# ARKnew.net
KiCad netlist of a schematic drawn in EAGLE
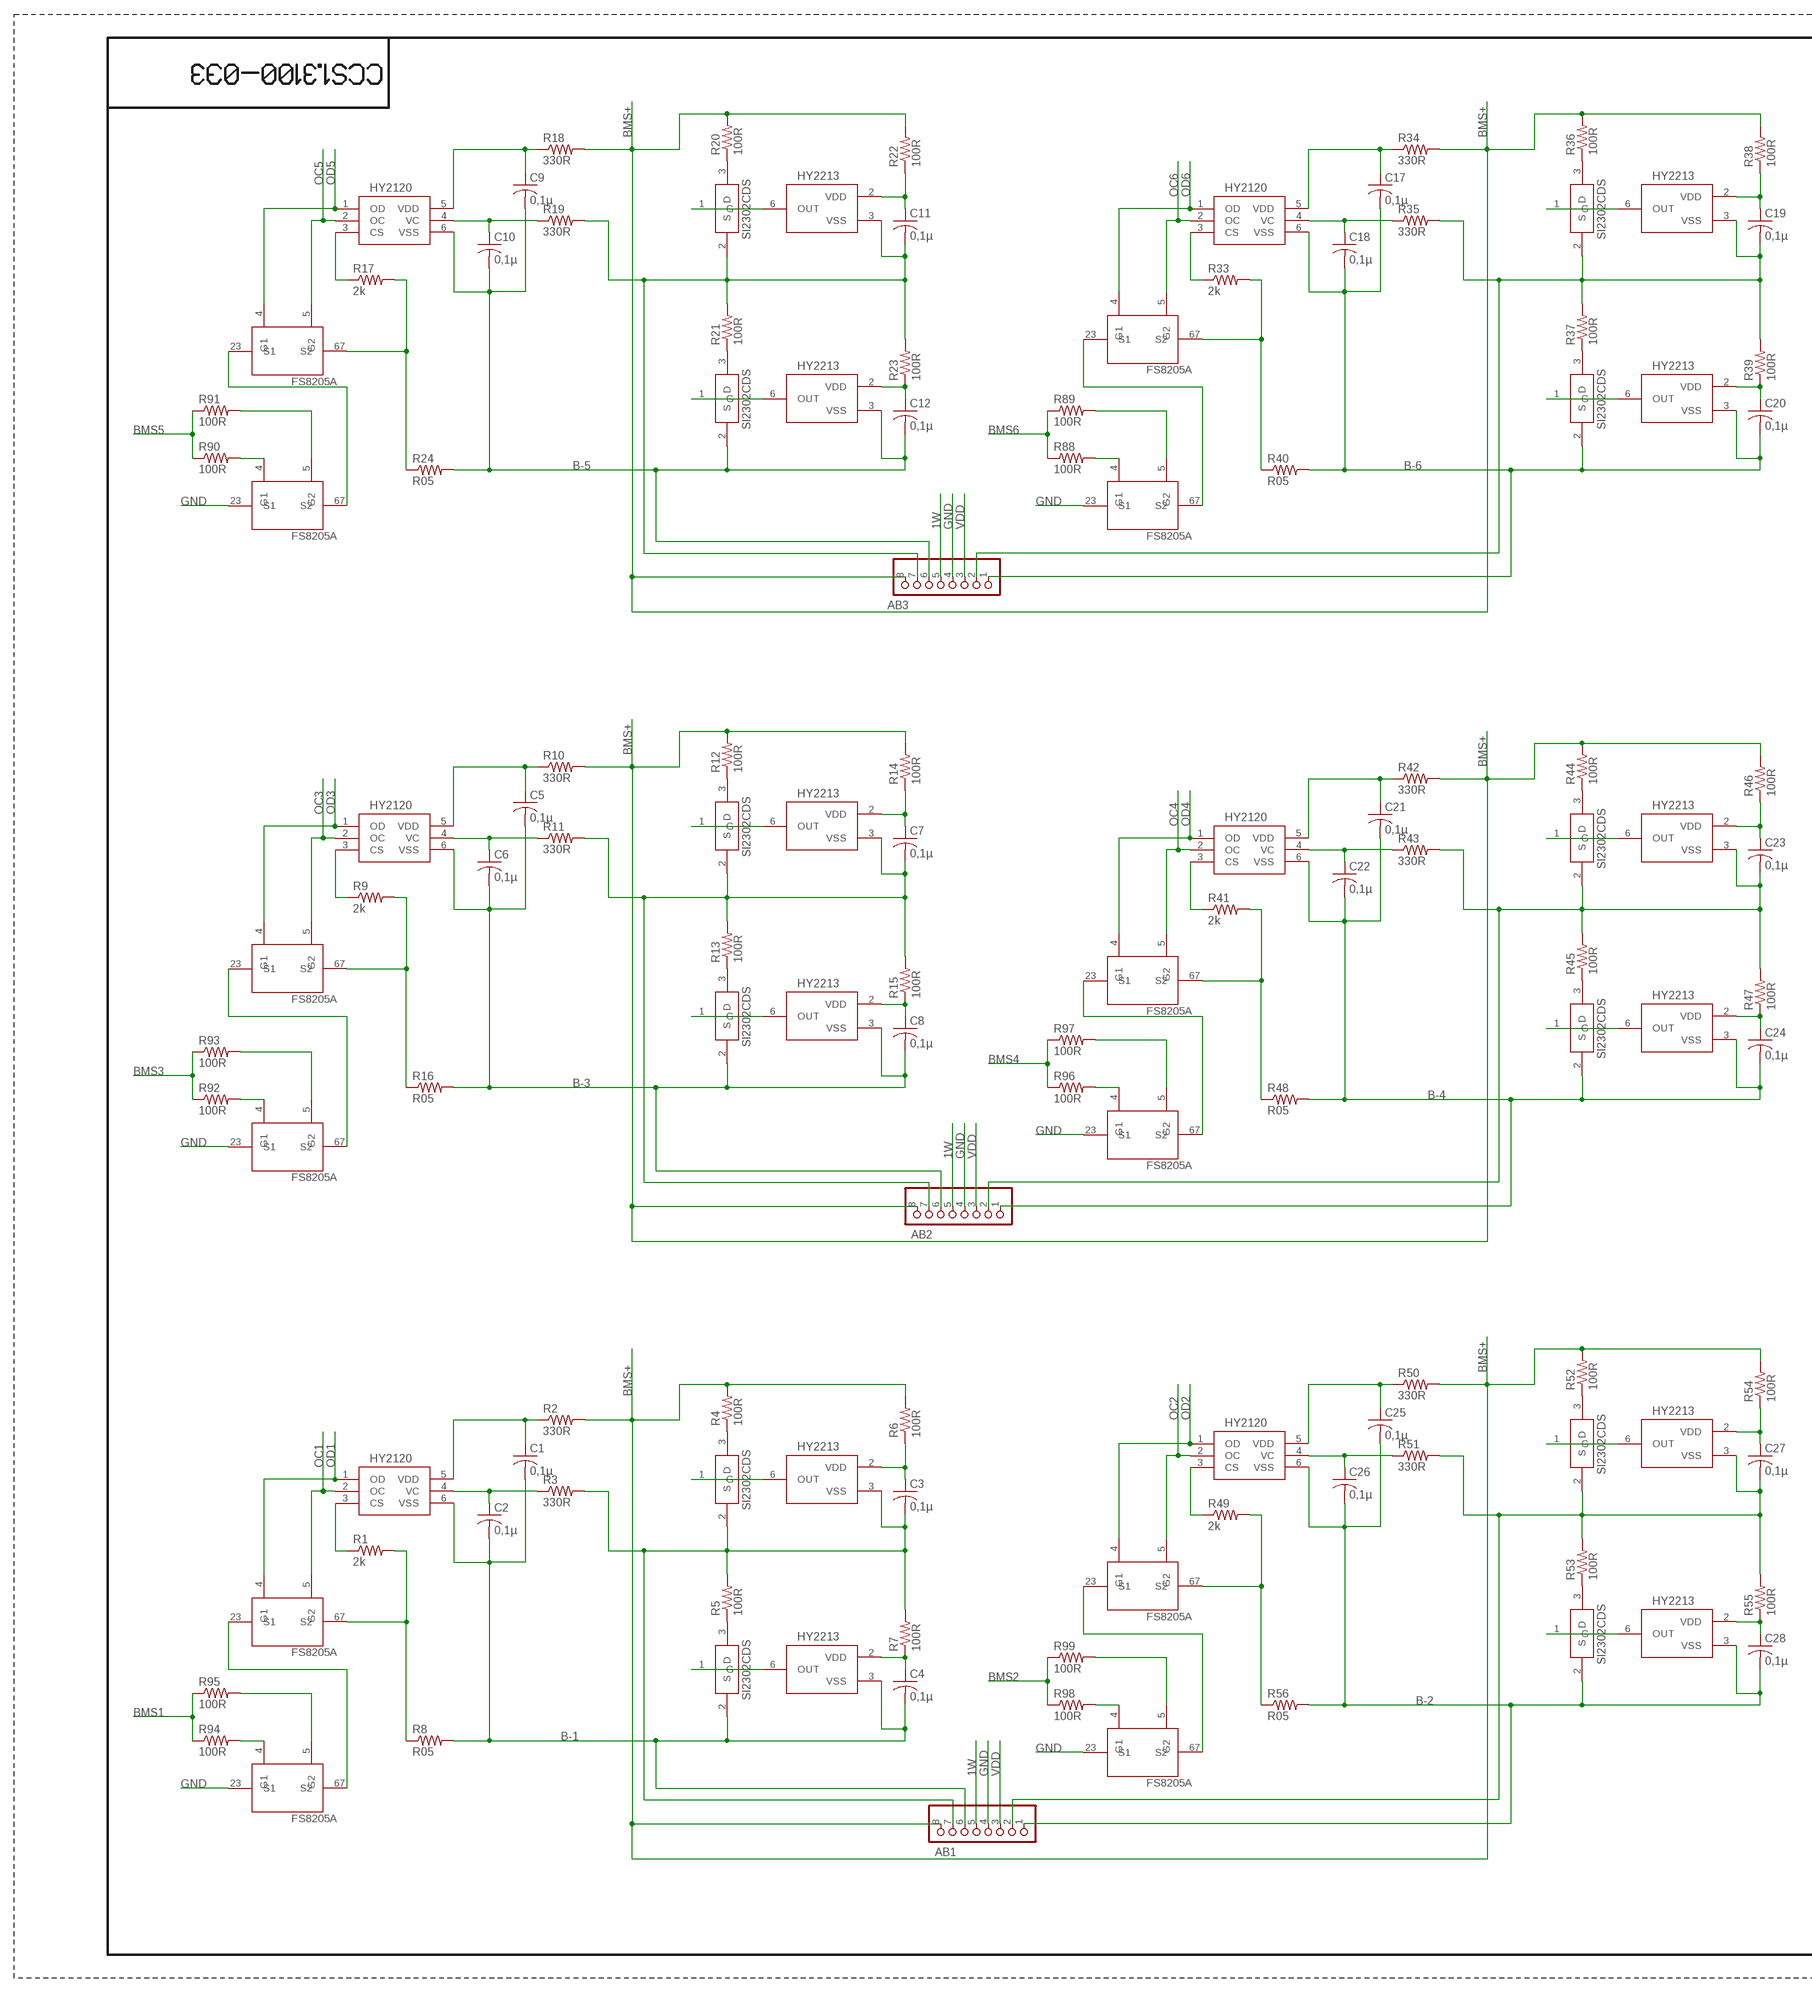
[diagram p0: schematic, sheet 1, part 1 of 2]
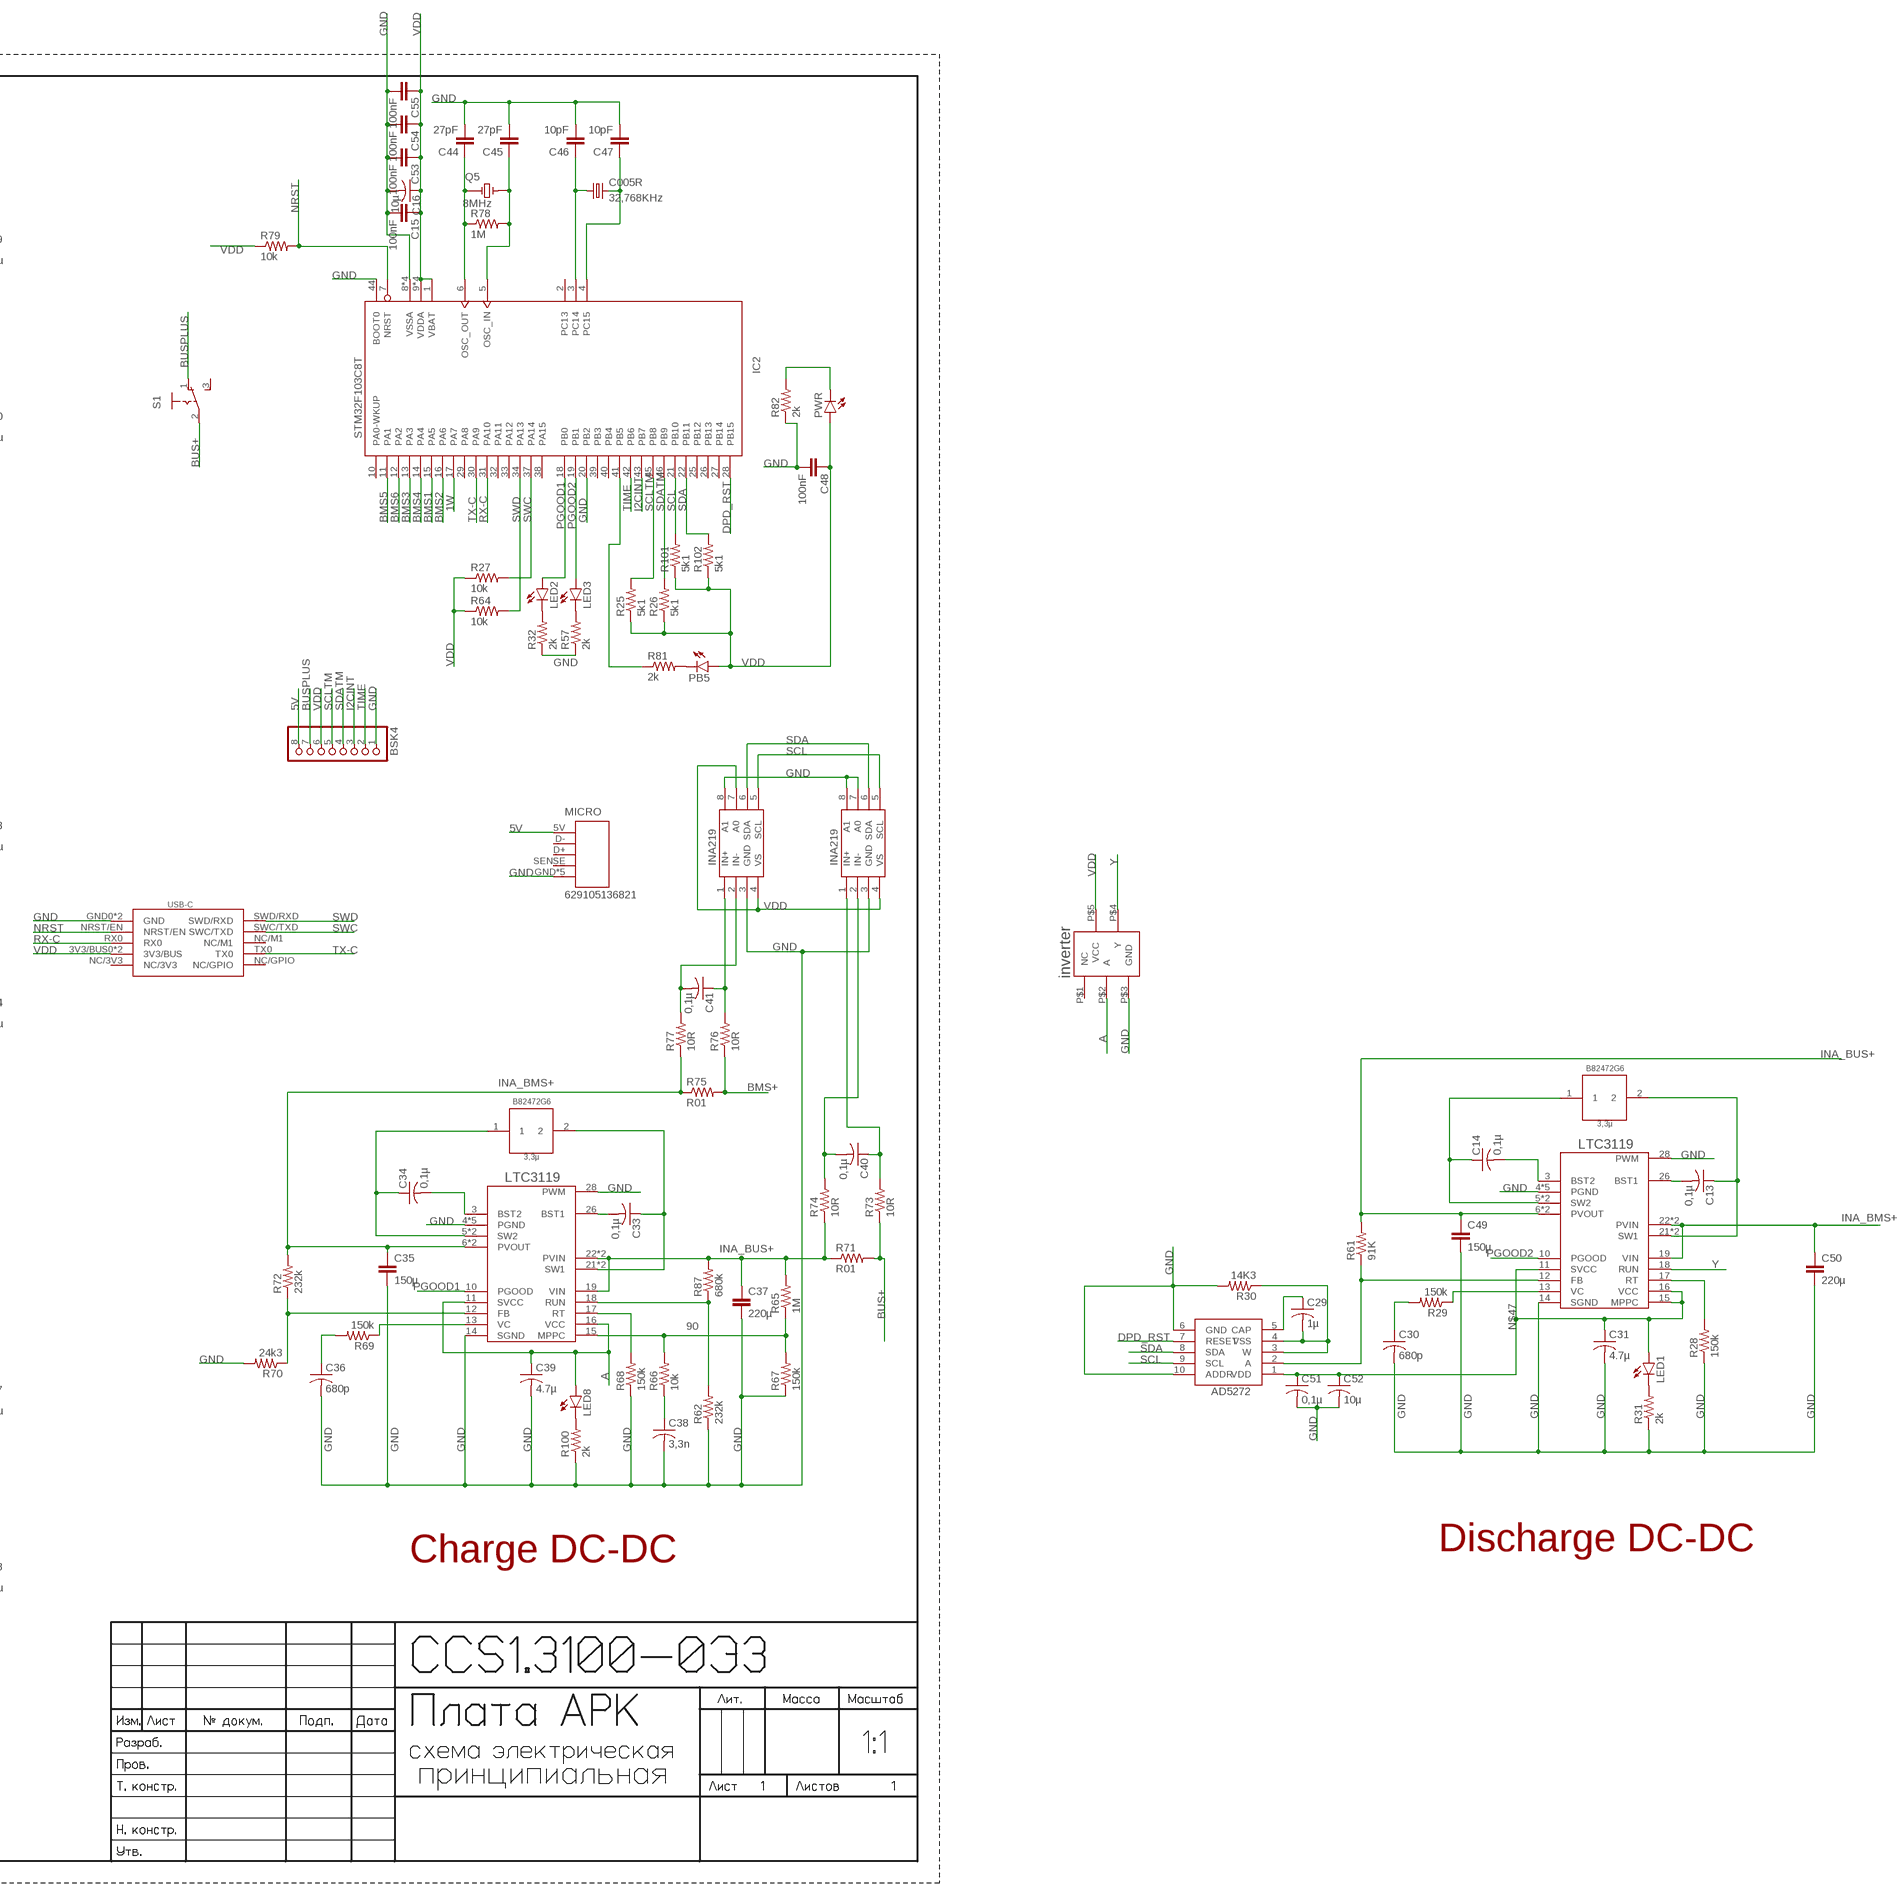
[diagram p1: schematic, sheet 1, part 2 of 2]

(export (version "E")
  (design (tool "Eeschema 10.0.6"))
  (components
    (comp (ref "3,3µH")
      (value "3,3µ")
      (footprint "eagle-import:B82472G6")
      (libsource (lib "eagle-import") (part "B82472G6"))
    )
    (comp (ref "3,3µH1")
      (value "3,3µ")
      (footprint "eagle-import:B82472G6")
      (libsource (lib "eagle-import") (part "B82472G6"))
    )
    (comp (ref "AB1")
      (value "PINHD-1X8")
      (footprint "eagle-import:1X08")
      (libsource (lib "eagle-import") (part "PINHD-1X8"))
    )
    (comp (ref "AB2")
      (value "PINHD-1X8")
      (footprint "eagle-import:1X08")
      (libsource (lib "eagle-import") (part "PINHD-1X8"))
    )
    (comp (ref "AB3")
      (value "PINHD-1X8")
      (footprint "eagle-import:1X08")
      (libsource (lib "eagle-import") (part "PINHD-1X8"))
    )
    (comp (ref "AD5272#2")
      (value "AD5272")
      (footprint "eagle-import:AD5272")
      (libsource (lib "eagle-import") (part "AD5272"))
    )
    (comp (ref "BSK4")
      (value "PINHD-1X8")
      (footprint "eagle-import:1X08")
      (libsource (lib "eagle-import") (part "PINHD-1X8"))
    )
    (comp (ref "C1")
      (value "0,1µ")
      (footprint "eagle-import:C0603")
      (libsource (lib "eagle-import") (part "C-USC0603"))
    )
    (comp (ref "C2")
      (value "0,1µ")
      (footprint "eagle-import:C0603")
      (libsource (lib "eagle-import") (part "C-USC0603"))
    )
    (comp (ref "C3")
      (value "0,1µ")
      (footprint "eagle-import:C0603")
      (libsource (lib "eagle-import") (part "C-USC0603"))
    )
    (comp (ref "C4")
      (value "0,1µ")
      (footprint "eagle-import:C0603")
      (libsource (lib "eagle-import") (part "C-USC0603"))
    )
    (comp (ref "C5")
      (value "0,1µ")
      (footprint "eagle-import:C0603")
      (libsource (lib "eagle-import") (part "C-USC0603"))
    )
    (comp (ref "C005R")
      (value "32,768KHz")
      (footprint "eagle-import:C005R")
      (libsource (lib "eagle-import") (part "C005R"))
    )
    (comp (ref "C6")
      (value "0,1µ")
      (footprint "eagle-import:C0603")
      (libsource (lib "eagle-import") (part "C-USC0603"))
    )
    (comp (ref "C7")
      (value "0,1µ")
      (footprint "eagle-import:C0603")
      (libsource (lib "eagle-import") (part "C-USC0603"))
    )
    (comp (ref "C8")
      (value "0,1µ")
      (footprint "eagle-import:C0603")
      (libsource (lib "eagle-import") (part "C-USC0603"))
    )
    (comp (ref "C9")
      (value "0,1µ")
      (footprint "eagle-import:C0603")
      (libsource (lib "eagle-import") (part "C-USC0603"))
    )
    (comp (ref "C10")
      (value "0,1µ")
      (footprint "eagle-import:C0603")
      (libsource (lib "eagle-import") (part "C-USC0603"))
    )
    (comp (ref "C11")
      (value "0,1µ")
      (footprint "eagle-import:C0603")
      (libsource (lib "eagle-import") (part "C-USC0603"))
    )
    (comp (ref "C12")
      (value "0,1µ")
      (footprint "eagle-import:C0603")
      (libsource (lib "eagle-import") (part "C-USC0603"))
    )
    (comp (ref "C13")
      (value "0,1µ")
      (footprint "eagle-import:C0603")
      (libsource (lib "eagle-import") (part "C-USC0603"))
    )
    (comp (ref "C14")
      (value "0,1µ")
      (footprint "eagle-import:C0603")
      (libsource (lib "eagle-import") (part "C-USC0603"))
    )
    (comp (ref "C15")
      (value "100nF")
      (footprint "eagle-import:C0603")
      (libsource (lib "eagle-import") (part "C-EUC0603"))
    )
    (comp (ref "C16")
      (value "10µ")
      (footprint "eagle-import:C1206")
      (libsource (lib "eagle-import") (part "C-USC1206"))
    )
    (comp (ref "C17")
      (value "0,1µ")
      (footprint "eagle-import:C0603")
      (libsource (lib "eagle-import") (part "C-USC0603"))
    )
    (comp (ref "C18")
      (value "0,1µ")
      (footprint "eagle-import:C0603")
      (libsource (lib "eagle-import") (part "C-USC0603"))
    )
    (comp (ref "C19")
      (value "0,1µ")
      (footprint "eagle-import:C0603")
      (libsource (lib "eagle-import") (part "C-USC0603"))
    )
    (comp (ref "C20")
      (value "0,1µ")
      (footprint "eagle-import:C0603")
      (libsource (lib "eagle-import") (part "C-USC0603"))
    )
    (comp (ref "C21")
      (value "0,1µ")
      (footprint "eagle-import:C0603")
      (libsource (lib "eagle-import") (part "C-USC0603"))
    )
    (comp (ref "C22")
      (value "0,1µ")
      (footprint "eagle-import:C0603")
      (libsource (lib "eagle-import") (part "C-USC0603"))
    )
    (comp (ref "C23")
      (value "0,1µ")
      (footprint "eagle-import:C0603")
      (libsource (lib "eagle-import") (part "C-USC0603"))
    )
    (comp (ref "C24")
      (value "0,1µ")
      (footprint "eagle-import:C0603")
      (libsource (lib "eagle-import") (part "C-USC0603"))
    )
    (comp (ref "C25")
      (value "0,1µ")
      (footprint "eagle-import:C0603")
      (libsource (lib "eagle-import") (part "C-USC0603"))
    )
    (comp (ref "C26")
      (value "0,1µ")
      (footprint "eagle-import:C0603")
      (libsource (lib "eagle-import") (part "C-USC0603"))
    )
    (comp (ref "C27")
      (value "0,1µ")
      (footprint "eagle-import:C0603")
      (libsource (lib "eagle-import") (part "C-USC0603"))
    )
    (comp (ref "C28")
      (value "0,1µ")
      (footprint "eagle-import:C0603")
      (libsource (lib "eagle-import") (part "C-USC0603"))
    )
    (comp (ref "C29")
      (value "1µ")
      (footprint "eagle-import:C0603")
      (libsource (lib "eagle-import") (part "C-USC0603"))
    )
    (comp (ref "C30")
      (value "680p")
      (footprint "eagle-import:C0603")
      (libsource (lib "eagle-import") (part "C-USC0603"))
    )
    (comp (ref "C31")
      (value "4.7µ")
      (footprint "eagle-import:C1206")
      (libsource (lib "eagle-import") (part "C-USC1206"))
    )
    (comp (ref "C33")
      (value "0,1µ")
      (footprint "eagle-import:C0603")
      (libsource (lib "eagle-import") (part "C-USC0603"))
    )
    (comp (ref "C34")
      (value "0,1µ")
      (footprint "eagle-import:C0603")
      (libsource (lib "eagle-import") (part "C-USC0603"))
    )
    (comp (ref "C35")
      (value "150µ")
      (footprint "eagle-import:ECAP150")
      (libsource (lib "eagle-import") (part "ECAPECAP150"))
    )
    (comp (ref "C36")
      (value "680p")
      (footprint "eagle-import:C0603")
      (libsource (lib "eagle-import") (part "C-USC0603"))
    )
    (comp (ref "C37")
      (value "220µ")
      (footprint "eagle-import:ECAP220")
      (libsource (lib "eagle-import") (part "ECAPECAP220"))
    )
    (comp (ref "C38")
      (value "3,3n")
      (footprint "eagle-import:C0603")
      (libsource (lib "eagle-import") (part "C-USC0603"))
    )
    (comp (ref "C39")
      (value "4.7µ")
      (footprint "eagle-import:C1206")
      (libsource (lib "eagle-import") (part "C-USC1206"))
    )
    (comp (ref "C40")
      (value "0,1µ")
      (footprint "eagle-import:C0603")
      (libsource (lib "eagle-import") (part "C-USC0603"))
    )
    (comp (ref "C41")
      (value "0,1µ")
      (footprint "eagle-import:C0603")
      (libsource (lib "eagle-import") (part "C-USC0603"))
    )
    (comp (ref "C44")
      (value "27pF")
      (footprint "eagle-import:C0603")
      (libsource (lib "eagle-import") (part "C-EUC0603"))
    )
    (comp (ref "C45")
      (value "27pF")
      (footprint "eagle-import:C0603")
      (libsource (lib "eagle-import") (part "C-EUC0603"))
    )
    (comp (ref "C46")
      (value "10pF")
      (footprint "eagle-import:C0603")
      (libsource (lib "eagle-import") (part "C-EUC0603"))
    )
    (comp (ref "C47")
      (value "10pF")
      (footprint "eagle-import:C0603")
      (libsource (lib "eagle-import") (part "C-EUC0603"))
    )
    (comp (ref "C48")
      (value "100nF")
      (footprint "eagle-import:C0603")
      (libsource (lib "eagle-import") (part "C-EUC0603"))
    )
    (comp (ref "C49")
      (value "150µ")
      (footprint "eagle-import:ECAP150")
      (libsource (lib "eagle-import") (part "ECAPECAP150"))
    )
    (comp (ref "C50")
      (value "220µ")
      (footprint "eagle-import:ECAP220")
      (libsource (lib "eagle-import") (part "ECAPECAP220"))
    )
    (comp (ref "C51")
      (value "0,1µ")
      (footprint "eagle-import:C0603")
      (libsource (lib "eagle-import") (part "C-USC0603"))
    )
    (comp (ref "C52")
      (value "10µ")
      (footprint "eagle-import:C1206")
      (libsource (lib "eagle-import") (part "C-USC1206"))
    )
    (comp (ref "C53")
      (value "100nF")
      (footprint "eagle-import:C0603")
      (libsource (lib "eagle-import") (part "C-EUC0603"))
    )
    (comp (ref "C54")
      (value "100nF")
      (footprint "eagle-import:C0603")
      (libsource (lib "eagle-import") (part "C-EUC0603"))
    )
    (comp (ref "C55")
      (value "100nF")
      (footprint "eagle-import:C0603")
      (libsource (lib "eagle-import") (part "C-EUC0603"))
    )
    (comp (ref "IC2")
      (value "STM32F103C8T")
      (footprint "eagle-import:LQFP48")
      (libsource (lib "eagle-import") (part "STM32F103CT8"))
    )
    (comp (ref "INA219#1")
      (value "INA219AID")
      (footprint "eagle-import:INA219AID")
      (libsource (lib "eagle-import") (part "INA219AID"))
    )
    (comp (ref "LED1")
      (value "LEDCHIPLED_0603")
      (footprint "eagle-import:CHIPLED_0603")
      (libsource (lib "eagle-import") (part "LEDCHIPLED_0603"))
    )
    (comp (ref "LED2")
      (value "LEDCHIPLED_0603")
      (footprint "eagle-import:CHIPLED_0603")
      (libsource (lib "eagle-import") (part "LEDCHIPLED_0603"))
    )
    (comp (ref "LED3")
      (value "LEDCHIPLED_0603")
      (footprint "eagle-import:CHIPLED_0603")
      (libsource (lib "eagle-import") (part "LEDCHIPLED_0603"))
    )
    (comp (ref "LED8")
      (value "LEDCHIPLED_0603")
      (footprint "eagle-import:CHIPLED_0603")
      (libsource (lib "eagle-import") (part "LEDCHIPLED_0603"))
    )
    (comp (ref "MICRO")
      (value "629105136821")
      (footprint "eagle-import:629105136821")
      (libsource (lib "eagle-import") (part "629105136821"))
    )
    (comp (ref "PB5")
      (value "LEDCHIPLED_0603")
      (footprint "eagle-import:CHIPLED_0603")
      (libsource (lib "eagle-import") (part "LEDCHIPLED_0603"))
    )
    (comp (ref "PWR")
      (value "LEDCHIPLED_0603")
      (footprint "eagle-import:CHIPLED_0603")
      (libsource (lib "eagle-import") (part "LEDCHIPLED_0603"))
    )
    (comp (ref "Q5")
      (value "8MHz")
      (footprint "eagle-import:XTAL_9C-8.000MEEJ-T")
      (fields (field (name "MF") "TXC CORPORATION") (field (name "MP") "9C-8.000MEEJ-T"))
      (libsource (lib "eagle-import") (part "9C-8.000MEEJ-T"))
    )
    (comp (ref "R1")
      (value "2k")
      (footprint "eagle-import:R0603")
      (libsource (lib "eagle-import") (part "resistor_348_R-US_R0603"))
    )
    (comp (ref "R2")
      (value "330R")
      (footprint "eagle-import:R0603")
      (libsource (lib "eagle-import") (part "resistor_348_R-US_R0603"))
    )
    (comp (ref "R3")
      (value "330R")
      (footprint "eagle-import:R0603")
      (libsource (lib "eagle-import") (part "resistor_348_R-US_R0603"))
    )
    (comp (ref "R4")
      (value "100R")
      (footprint "eagle-import:R0603")
      (libsource (lib "eagle-import") (part "resistor_348_R-US_R0603"))
    )
    (comp (ref "R5")
      (value "100R")
      (footprint "eagle-import:R0603")
      (libsource (lib "eagle-import") (part "resistor_348_R-US_R0603"))
    )
    (comp (ref "R6")
      (value "100R")
      (footprint "eagle-import:R0603")
      (libsource (lib "eagle-import") (part "resistor_348_R-US_R0603"))
    )
    (comp (ref "R7")
      (value "100R")
      (footprint "eagle-import:R0603")
      (libsource (lib "eagle-import") (part "resistor_348_R-US_R0603"))
    )
    (comp (ref "R8")
      (value "R05")
      (footprint "eagle-import:R2512")
      (libsource (lib "eagle-import") (part "R-US_R2512"))
    )
    (comp (ref "R9")
      (value "2k")
      (footprint "eagle-import:R0603")
      (libsource (lib "eagle-import") (part "resistor_348_R-US_R0603"))
    )
    (comp (ref "R10")
      (value "330R")
      (footprint "eagle-import:R0603")
      (libsource (lib "eagle-import") (part "resistor_348_R-US_R0603"))
    )
    (comp (ref "R11")
      (value "330R")
      (footprint "eagle-import:R0603")
      (libsource (lib "eagle-import") (part "resistor_348_R-US_R0603"))
    )
    (comp (ref "R12")
      (value "100R")
      (footprint "eagle-import:R0603")
      (libsource (lib "eagle-import") (part "resistor_348_R-US_R0603"))
    )
    (comp (ref "R13")
      (value "100R")
      (footprint "eagle-import:R0603")
      (libsource (lib "eagle-import") (part "resistor_348_R-US_R0603"))
    )
    (comp (ref "R14")
      (value "100R")
      (footprint "eagle-import:R0603")
      (libsource (lib "eagle-import") (part "resistor_348_R-US_R0603"))
    )
    (comp (ref "R15")
      (value "100R")
      (footprint "eagle-import:R0603")
      (libsource (lib "eagle-import") (part "resistor_348_R-US_R0603"))
    )
    (comp (ref "R16")
      (value "R05")
      (footprint "eagle-import:R2512")
      (libsource (lib "eagle-import") (part "R-US_R2512"))
    )
    (comp (ref "R17")
      (value "2k")
      (footprint "eagle-import:R0603")
      (libsource (lib "eagle-import") (part "resistor_348_R-US_R0603"))
    )
    (comp (ref "R18")
      (value "330R")
      (footprint "eagle-import:R0603")
      (libsource (lib "eagle-import") (part "resistor_348_R-US_R0603"))
    )
    (comp (ref "R19")
      (value "330R")
      (footprint "eagle-import:R0603")
      (libsource (lib "eagle-import") (part "resistor_348_R-US_R0603"))
    )
    (comp (ref "R20")
      (value "100R")
      (footprint "eagle-import:R0603")
      (libsource (lib "eagle-import") (part "resistor_348_R-US_R0603"))
    )
    (comp (ref "R21")
      (value "100R")
      (footprint "eagle-import:R0603")
      (libsource (lib "eagle-import") (part "resistor_348_R-US_R0603"))
    )
    (comp (ref "R22")
      (value "100R")
      (footprint "eagle-import:R0603")
      (libsource (lib "eagle-import") (part "resistor_348_R-US_R0603"))
    )
    (comp (ref "R23")
      (value "100R")
      (footprint "eagle-import:R0603")
      (libsource (lib "eagle-import") (part "resistor_348_R-US_R0603"))
    )
    (comp (ref "R24")
      (value "R05")
      (footprint "eagle-import:R2512")
      (libsource (lib "eagle-import") (part "R-US_R2512"))
    )
    (comp (ref "R25")
      (value "5k1")
      (footprint "eagle-import:R0603")
      (libsource (lib "eagle-import") (part "resistor_348_R-US_R0603"))
    )
    (comp (ref "R26")
      (value "5k1")
      (footprint "eagle-import:R0603")
      (libsource (lib "eagle-import") (part "resistor_348_R-US_R0603"))
    )
    (comp (ref "R27")
      (value "10k")
      (footprint "eagle-import:R0603")
      (libsource (lib "eagle-import") (part "resistor_348_R-US_R0603"))
    )
    (comp (ref "R28")
      (value "150k")
      (footprint "eagle-import:R0603")
      (libsource (lib "eagle-import") (part "resistor_348_R-US_R0603"))
    )
    (comp (ref "R29")
      (value "150k")
      (footprint "eagle-import:R0603")
      (libsource (lib "eagle-import") (part "resistor_348_R-US_R0603"))
    )
    (comp (ref "R30")
      (value "14K3")
      (footprint "eagle-import:R0603")
      (libsource (lib "eagle-import") (part "resistor_348_R-US_R0603"))
    )
    (comp (ref "R31")
      (value "2k")
      (footprint "eagle-import:R0603")
      (libsource (lib "eagle-import") (part "resistor_348_R-US_R0603"))
    )
    (comp (ref "R32")
      (value "2k")
      (footprint "eagle-import:R0603")
      (libsource (lib "eagle-import") (part "resistor_348_R-US_R0603"))
    )
    (comp (ref "R33")
      (value "2k")
      (footprint "eagle-import:R0603")
      (libsource (lib "eagle-import") (part "resistor_348_R-US_R0603"))
    )
    (comp (ref "R34")
      (value "330R")
      (footprint "eagle-import:R0603")
      (libsource (lib "eagle-import") (part "resistor_348_R-US_R0603"))
    )
    (comp (ref "R35")
      (value "330R")
      (footprint "eagle-import:R0603")
      (libsource (lib "eagle-import") (part "resistor_348_R-US_R0603"))
    )
    (comp (ref "R36")
      (value "100R")
      (footprint "eagle-import:R0603")
      (libsource (lib "eagle-import") (part "resistor_348_R-US_R0603"))
    )
    (comp (ref "R37")
      (value "100R")
      (footprint "eagle-import:R0603")
      (libsource (lib "eagle-import") (part "resistor_348_R-US_R0603"))
    )
    (comp (ref "R38")
      (value "100R")
      (footprint "eagle-import:R0603")
      (libsource (lib "eagle-import") (part "resistor_348_R-US_R0603"))
    )
    (comp (ref "R39")
      (value "100R")
      (footprint "eagle-import:R0603")
      (libsource (lib "eagle-import") (part "resistor_348_R-US_R0603"))
    )
    (comp (ref "R40")
      (value "R05")
      (footprint "eagle-import:R2512")
      (libsource (lib "eagle-import") (part "R-US_R2512"))
    )
    (comp (ref "R41")
      (value "2k")
      (footprint "eagle-import:R0603")
      (libsource (lib "eagle-import") (part "resistor_348_R-US_R0603"))
    )
    (comp (ref "R42")
      (value "330R")
      (footprint "eagle-import:R0603")
      (libsource (lib "eagle-import") (part "resistor_348_R-US_R0603"))
    )
    (comp (ref "R43")
      (value "330R")
      (footprint "eagle-import:R0603")
      (libsource (lib "eagle-import") (part "resistor_348_R-US_R0603"))
    )
    (comp (ref "R44")
      (value "100R")
      (footprint "eagle-import:R0603")
      (libsource (lib "eagle-import") (part "resistor_348_R-US_R0603"))
    )
    (comp (ref "R45")
      (value "100R")
      (footprint "eagle-import:R0603")
      (libsource (lib "eagle-import") (part "resistor_348_R-US_R0603"))
    )
    (comp (ref "R46")
      (value "100R")
      (footprint "eagle-import:R0603")
      (libsource (lib "eagle-import") (part "resistor_348_R-US_R0603"))
    )
    (comp (ref "R47")
      (value "100R")
      (footprint "eagle-import:R0603")
      (libsource (lib "eagle-import") (part "resistor_348_R-US_R0603"))
    )
    (comp (ref "R48")
      (value "R05")
      (footprint "eagle-import:R2512")
      (libsource (lib "eagle-import") (part "R-US_R2512"))
    )
    (comp (ref "R49")
      (value "2k")
      (footprint "eagle-import:R0603")
      (libsource (lib "eagle-import") (part "resistor_348_R-US_R0603"))
    )
    (comp (ref "R50")
      (value "330R")
      (footprint "eagle-import:R0603")
      (libsource (lib "eagle-import") (part "resistor_348_R-US_R0603"))
    )
    (comp (ref "R51")
      (value "330R")
      (footprint "eagle-import:R0603")
      (libsource (lib "eagle-import") (part "resistor_348_R-US_R0603"))
    )
    (comp (ref "R52")
      (value "100R")
      (footprint "eagle-import:R0603")
      (libsource (lib "eagle-import") (part "resistor_348_R-US_R0603"))
    )
    (comp (ref "R53")
      (value "100R")
      (footprint "eagle-import:R0603")
      (libsource (lib "eagle-import") (part "resistor_348_R-US_R0603"))
    )
    (comp (ref "R54")
      (value "100R")
      (footprint "eagle-import:R0603")
      (libsource (lib "eagle-import") (part "resistor_348_R-US_R0603"))
    )
    (comp (ref "R55")
      (value "100R")
      (footprint "eagle-import:R0603")
      (libsource (lib "eagle-import") (part "resistor_348_R-US_R0603"))
    )
    (comp (ref "R56")
      (value "R05")
      (footprint "eagle-import:R2512")
      (libsource (lib "eagle-import") (part "R-US_R2512"))
    )
    (comp (ref "R57")
      (value "2k")
      (footprint "eagle-import:R0603")
      (libsource (lib "eagle-import") (part "resistor_348_R-US_R0603"))
    )
    (comp (ref "R61")
      (value "91K")
      (footprint "eagle-import:R0603")
      (libsource (lib "eagle-import") (part "resistor_348_R-US_R0603"))
    )
    (comp (ref "R62")
      (value "232k")
      (footprint "eagle-import:R0603")
      (libsource (lib "eagle-import") (part "resistor_348_R-US_R0603"))
    )
    (comp (ref "R64")
      (value "10k")
      (footprint "eagle-import:R0603")
      (libsource (lib "eagle-import") (part "resistor_348_R-US_R0603"))
    )
    (comp (ref "R65")
      (value "1M")
      (footprint "eagle-import:R0603")
      (libsource (lib "eagle-import") (part "resistor_348_R-US_R0603"))
    )
    (comp (ref "R66")
      (value "10k")
      (footprint "eagle-import:R0603")
      (libsource (lib "eagle-import") (part "resistor_348_R-US_R0603"))
    )
    (comp (ref "R67")
      (value "150k")
      (footprint "eagle-import:R0603")
      (libsource (lib "eagle-import") (part "resistor_348_R-US_R0603"))
    )
    (comp (ref "R68")
      (value "150k")
      (footprint "eagle-import:R0603")
      (libsource (lib "eagle-import") (part "resistor_348_R-US_R0603"))
    )
    (comp (ref "R69")
      (value "150k")
      (footprint "eagle-import:R0603")
      (libsource (lib "eagle-import") (part "resistor_348_R-US_R0603"))
    )
    (comp (ref "R70")
      (value "24k3")
      (footprint "eagle-import:R0603")
      (libsource (lib "eagle-import") (part "resistor_348_R-US_R0603"))
    )
    (comp (ref "R71")
      (value "R01")
      (footprint "eagle-import:R2512")
      (libsource (lib "eagle-import") (part "R-US_R2512"))
    )
    (comp (ref "R72")
      (value "232k")
      (footprint "eagle-import:R0603")
      (libsource (lib "eagle-import") (part "resistor_348_R-US_R0603"))
    )
    (comp (ref "R73")
      (value "10R")
      (footprint "eagle-import:R0603")
      (libsource (lib "eagle-import") (part "resistor_348_R-US_R0603"))
    )
    (comp (ref "R74")
      (value "10R")
      (footprint "eagle-import:R0603")
      (libsource (lib "eagle-import") (part "resistor_348_R-US_R0603"))
    )
    (comp (ref "R75")
      (value "R01")
      (footprint "eagle-import:R2512")
      (libsource (lib "eagle-import") (part "R-US_R2512"))
    )
    (comp (ref "R76")
      (value "10R")
      (footprint "eagle-import:R0603")
      (libsource (lib "eagle-import") (part "resistor_348_R-US_R0603"))
    )
    (comp (ref "R77")
      (value "10R")
      (footprint "eagle-import:R0603")
      (libsource (lib "eagle-import") (part "resistor_348_R-US_R0603"))
    )
    (comp (ref "R78")
      (value "1M")
      (footprint "eagle-import:R0603")
      (libsource (lib "eagle-import") (part "resistor_348_R-US_R0603"))
    )
    (comp (ref "R79")
      (value "10k")
      (footprint "eagle-import:R0603")
      (libsource (lib "eagle-import") (part "resistor_348_R-US_R0603"))
    )
    (comp (ref "R81")
      (value "2k")
      (footprint "eagle-import:R0603")
      (libsource (lib "eagle-import") (part "resistor_348_R-US_R0603"))
    )
    (comp (ref "R82")
      (value "2k")
      (footprint "eagle-import:R0603")
      (libsource (lib "eagle-import") (part "resistor_348_R-US_R0603"))
    )
    (comp (ref "R87")
      (value "680k")
      (footprint "eagle-import:R0603")
      (libsource (lib "eagle-import") (part "resistor_348_R-US_R0603"))
    )
    (comp (ref "R88")
      (value "100R")
      (footprint "eagle-import:R0603")
      (libsource (lib "eagle-import") (part "resistor_348_R-US_R0603"))
    )
    (comp (ref "R89")
      (value "100R")
      (footprint "eagle-import:R0603")
      (libsource (lib "eagle-import") (part "resistor_348_R-US_R0603"))
    )
    (comp (ref "R90")
      (value "100R")
      (footprint "eagle-import:R0603")
      (libsource (lib "eagle-import") (part "resistor_348_R-US_R0603"))
    )
    (comp (ref "R91")
      (value "100R")
      (footprint "eagle-import:R0603")
      (libsource (lib "eagle-import") (part "resistor_348_R-US_R0603"))
    )
    (comp (ref "R92")
      (value "100R")
      (footprint "eagle-import:R0603")
      (libsource (lib "eagle-import") (part "resistor_348_R-US_R0603"))
    )
    (comp (ref "R93")
      (value "100R")
      (footprint "eagle-import:R0603")
      (libsource (lib "eagle-import") (part "resistor_348_R-US_R0603"))
    )
    (comp (ref "R94")
      (value "100R")
      (footprint "eagle-import:R0603")
      (libsource (lib "eagle-import") (part "resistor_348_R-US_R0603"))
    )
    (comp (ref "R95")
      (value "100R")
      (footprint "eagle-import:R0603")
      (libsource (lib "eagle-import") (part "resistor_348_R-US_R0603"))
    )
    (comp (ref "R96")
      (value "100R")
      (footprint "eagle-import:R0603")
      (libsource (lib "eagle-import") (part "resistor_348_R-US_R0603"))
    )
    (comp (ref "R97")
      (value "100R")
      (footprint "eagle-import:R0603")
      (libsource (lib "eagle-import") (part "resistor_348_R-US_R0603"))
    )
    (comp (ref "R98")
      (value "100R")
      (footprint "eagle-import:R0603")
      (libsource (lib "eagle-import") (part "resistor_348_R-US_R0603"))
    )
    (comp (ref "R99")
      (value "100R")
      (footprint "eagle-import:R0603")
      (libsource (lib "eagle-import") (part "resistor_348_R-US_R0603"))
    )
    (comp (ref "R100")
      (value "2k")
      (footprint "eagle-import:R0603")
      (libsource (lib "eagle-import") (part "resistor_348_R-US_R0603"))
    )
    (comp (ref "R101")
      (value "5k1")
      (footprint "eagle-import:R0603")
      (libsource (lib "eagle-import") (part "resistor_348_R-US_R0603"))
    )
    (comp (ref "R102")
      (value "5k1")
      (footprint "eagle-import:R0603")
      (libsource (lib "eagle-import") (part "resistor_348_R-US_R0603"))
    )
    (comp (ref "S1")
      (value "UNICS-SWITCH")
      (footprint "eagle-import:UNICS-SWITCH")
      (libsource (lib "eagle-import") (part "UNICS-SWITCH"))
    )
    (comp (ref "U$1")
      (value "FS8205A-")
      (footprint "eagle-import:FS8205A-")
      (libsource (lib "eagle-import") (part "FS8205A-"))
    )
    (comp (ref "U$2")
      (value "INVERTER")
      (footprint "eagle-import:INVERTER")
      (libsource (lib "eagle-import") (part "INVERTER"))
    )
    (comp (ref "U$3")
      (value "HY2120")
      (footprint "eagle-import:HY2120")
      (libsource (lib "eagle-import") (part "HY2120"))
    )
    (comp (ref "U$4")
      (value "HY2213")
      (footprint "eagle-import:HY2213")
      (libsource (lib "eagle-import") (part "HY2213"))
    )
    (comp (ref "U$5")
      (value "HY2213")
      (footprint "eagle-import:HY2213")
      (libsource (lib "eagle-import") (part "HY2213"))
    )
    (comp (ref "U$6")
      (value "SI2302CDS")
      (footprint "eagle-import:SI2302CDS")
      (libsource (lib "eagle-import") (part "SI2302CDS"))
    )
    (comp (ref "U$7")
      (value "SI2302CDS")
      (footprint "eagle-import:SI2302CDS")
      (libsource (lib "eagle-import") (part "SI2302CDS"))
    )
    (comp (ref "U$8")
      (value "FS8205A-")
      (footprint "eagle-import:FS8205A-")
      (libsource (lib "eagle-import") (part "FS8205A-"))
    )
    (comp (ref "U$9")
      (value "FS8205A-")
      (footprint "eagle-import:FS8205A-")
      (libsource (lib "eagle-import") (part "FS8205A-"))
    )
    (comp (ref "U$10")
      (value "HY2120")
      (footprint "eagle-import:HY2120")
      (libsource (lib "eagle-import") (part "HY2120"))
    )
    (comp (ref "U$11")
      (value "HY2213")
      (footprint "eagle-import:HY2213")
      (libsource (lib "eagle-import") (part "HY2213"))
    )
    (comp (ref "U$12")
      (value "HY2213")
      (footprint "eagle-import:HY2213")
      (libsource (lib "eagle-import") (part "HY2213"))
    )
    (comp (ref "U$13")
      (value "SI2302CDS")
      (footprint "eagle-import:SI2302CDS")
      (libsource (lib "eagle-import") (part "SI2302CDS"))
    )
    (comp (ref "U$14")
      (value "SI2302CDS")
      (footprint "eagle-import:SI2302CDS")
      (libsource (lib "eagle-import") (part "SI2302CDS"))
    )
    (comp (ref "U$15")
      (value "FS8205A-")
      (footprint "eagle-import:FS8205A-")
      (libsource (lib "eagle-import") (part "FS8205A-"))
    )
    (comp (ref "U$16")
      (value "LTC3119")
      (footprint "eagle-import:LTC3119")
      (libsource (lib "eagle-import") (part "LTC3119"))
    )
    (comp (ref "U$17")
      (value "HY2120")
      (footprint "eagle-import:HY2120")
      (libsource (lib "eagle-import") (part "HY2120"))
    )
    (comp (ref "U$18")
      (value "HY2213")
      (footprint "eagle-import:HY2213")
      (libsource (lib "eagle-import") (part "HY2213"))
    )
    (comp (ref "U$19")
      (value "HY2213")
      (footprint "eagle-import:HY2213")
      (libsource (lib "eagle-import") (part "HY2213"))
    )
    (comp (ref "U$20")
      (value "SI2302CDS")
      (footprint "eagle-import:SI2302CDS")
      (libsource (lib "eagle-import") (part "SI2302CDS"))
    )
    (comp (ref "U$21")
      (value "SI2302CDS")
      (footprint "eagle-import:SI2302CDS")
      (libsource (lib "eagle-import") (part "SI2302CDS"))
    )
    (comp (ref "U$22")
      (value "FS8205A-")
      (footprint "eagle-import:FS8205A-")
      (libsource (lib "eagle-import") (part "FS8205A-"))
    )
    (comp (ref "U$23")
      (value "USB-C")
      (footprint "eagle-import:USB-C")
      (libsource (lib "eagle-import") (part "USB-C"))
    )
    (comp (ref "U$24")
      (value "FS8205A-")
      (footprint "eagle-import:FS8205A-")
      (libsource (lib "eagle-import") (part "FS8205A-"))
    )
    (comp (ref "U$25")
      (value "FS8205A-")
      (footprint "eagle-import:FS8205A-")
      (libsource (lib "eagle-import") (part "FS8205A-"))
    )
    (comp (ref "U$26")
      (value "FS8205A-")
      (footprint "eagle-import:FS8205A-")
      (libsource (lib "eagle-import") (part "FS8205A-"))
    )
    (comp (ref "U$27")
      (value "FS8205A-")
      (footprint "eagle-import:FS8205A-")
      (libsource (lib "eagle-import") (part "FS8205A-"))
    )
    (comp (ref "U$28")
      (value "FS8205A-")
      (footprint "eagle-import:FS8205A-")
      (libsource (lib "eagle-import") (part "FS8205A-"))
    )
    (comp (ref "U$29")
      (value "FS8205A-")
      (footprint "eagle-import:FS8205A-")
      (libsource (lib "eagle-import") (part "FS8205A-"))
    )
    (comp (ref "U$30")
      (value "FS8205A-")
      (footprint "eagle-import:FS8205A-")
      (libsource (lib "eagle-import") (part "FS8205A-"))
    )
    (comp (ref "U$31")
      (value "HY2120")
      (footprint "eagle-import:HY2120")
      (libsource (lib "eagle-import") (part "HY2120"))
    )
    (comp (ref "U$32")
      (value "HY2213")
      (footprint "eagle-import:HY2213")
      (libsource (lib "eagle-import") (part "HY2213"))
    )
    (comp (ref "U$33")
      (value "HY2213")
      (footprint "eagle-import:HY2213")
      (libsource (lib "eagle-import") (part "HY2213"))
    )
    (comp (ref "U$34")
      (value "SI2302CDS")
      (footprint "eagle-import:SI2302CDS")
      (libsource (lib "eagle-import") (part "SI2302CDS"))
    )
    (comp (ref "U$35")
      (value "SI2302CDS")
      (footprint "eagle-import:SI2302CDS")
      (libsource (lib "eagle-import") (part "SI2302CDS"))
    )
    (comp (ref "U$38")
      (value "HY2120")
      (footprint "eagle-import:HY2120")
      (libsource (lib "eagle-import") (part "HY2120"))
    )
    (comp (ref "U$39")
      (value "HY2213")
      (footprint "eagle-import:HY2213")
      (libsource (lib "eagle-import") (part "HY2213"))
    )
    (comp (ref "U$40")
      (value "HY2213")
      (footprint "eagle-import:HY2213")
      (libsource (lib "eagle-import") (part "HY2213"))
    )
    (comp (ref "U$41")
      (value "SI2302CDS")
      (footprint "eagle-import:SI2302CDS")
      (libsource (lib "eagle-import") (part "SI2302CDS"))
    )
    (comp (ref "U$42")
      (value "SI2302CDS")
      (footprint "eagle-import:SI2302CDS")
      (libsource (lib "eagle-import") (part "SI2302CDS"))
    )
    (comp (ref "U$45")
      (value "HY2120")
      (footprint "eagle-import:HY2120")
      (libsource (lib "eagle-import") (part "HY2120"))
    )
    (comp (ref "U$46")
      (value "HY2213")
      (footprint "eagle-import:HY2213")
      (libsource (lib "eagle-import") (part "HY2213"))
    )
    (comp (ref "U$47")
      (value "HY2213")
      (footprint "eagle-import:HY2213")
      (libsource (lib "eagle-import") (part "HY2213"))
    )
    (comp (ref "U$48")
      (value "SI2302CDS")
      (footprint "eagle-import:SI2302CDS")
      (libsource (lib "eagle-import") (part "SI2302CDS"))
    )
    (comp (ref "U$49")
      (value "SI2302CDS")
      (footprint "eagle-import:SI2302CDS")
      (libsource (lib "eagle-import") (part "SI2302CDS"))
    )
    (comp (ref "U$57")
      (value "INA219AID")
      (footprint "eagle-import:INA219AID")
      (libsource (lib "eagle-import") (part "INA219AID"))
    )
    (comp (ref "U$59")
      (value "LTC3119")
      (footprint "eagle-import:LTC3119")
      (libsource (lib "eagle-import") (part "LTC3119"))
    )
  )
  (nets
    (net (code "1") (name "/1W") (class "Default")
      (node (ref "AB1") (pin "5") (pinfunction "5_5") (pintype "passive"))
      (node (ref "AB2") (pin "5") (pinfunction "5_5") (pintype "passive"))
      (node (ref "AB3") (pin "5") (pinfunction "5_5") (pintype "passive"))
      (node (ref "IC2") (pin "17") (pinfunction "PA7_17") (pintype "bidirectional"))
    )
    (net (code "2") (name "/5V") (class "Default")
      (node (ref "BSK4") (pin "8") (pinfunction "8_8") (pintype "passive"))
      (node (ref "MICRO") (pin "5V") (pinfunction "1_5V") (pintype "passive"))
    )
    (net (code "3") (name "/90") (class "Default")
      (node (ref "R65") (pin "1") (pinfunction "1_1") (pintype "passive"))
      (node (ref "R66") (pin "2") (pinfunction "2_2") (pintype "passive"))
      (node (ref "R67") (pin "2") (pinfunction "2_2") (pintype "passive"))
      (node (ref "U$59") (pin "15") (pinfunction "MPPC_15") (pintype "bidirectional"))
    )
    (net (code "4") (name "/A") (class "Default")
      (node (ref "C39") (pin "1") (pinfunction "1_1") (pintype "passive"))
      (node (ref "LED8") (pin "A") (pinfunction "A_A") (pintype "passive"))
      (node (ref "U$2") (pin "P$2") (pinfunction "A_P$2") (pintype "bidirectional"))
      (node (ref "U$59") (pin "11") (pinfunction "SVCC_11") (pintype "bidirectional"))
      (node (ref "U$59") (pin "16") (pinfunction "VCC_16") (pintype "bidirectional"))
    )
    (net (code "5") (name "/B-1") (class "Default")
      (node (ref "AB1") (pin "6") (pinfunction "6_6") (pintype "passive"))
      (node (ref "C1") (pin "2") (pinfunction "2_2") (pintype "passive"))
      (node (ref "C2") (pin "2") (pinfunction "2_2") (pintype "passive"))
      (node (ref "C4") (pin "2") (pinfunction "2_2") (pintype "passive"))
      (node (ref "R8") (pin "2") (pinfunction "2_2") (pintype "passive"))
      (node (ref "U$3") (pin "6") (pinfunction "VSS_6") (pintype "bidirectional"))
      (node (ref "U$5") (pin "3") (pinfunction "VSS_3") (pintype "bidirectional"))
      (node (ref "U$7") (pin "2") (pinfunction "S_2") (pintype "bidirectional"))
    )
    (net (code "6") (name "/B-2") (class "Default")
      (node (ref "AB1") (pin "1") (pinfunction "1_1") (pintype "passive"))
      (node (ref "C25") (pin "2") (pinfunction "2_2") (pintype "passive"))
      (node (ref "C26") (pin "2") (pinfunction "2_2") (pintype "passive"))
      (node (ref "C28") (pin "2") (pinfunction "2_2") (pintype "passive"))
      (node (ref "R56") (pin "2") (pinfunction "2_2") (pintype "passive"))
      (node (ref "U$45") (pin "6") (pinfunction "VSS_6") (pintype "bidirectional"))
      (node (ref "U$47") (pin "3") (pinfunction "VSS_3") (pintype "bidirectional"))
      (node (ref "U$49") (pin "2") (pinfunction "S_2") (pintype "bidirectional"))
    )
    (net (code "7") (name "/B-3") (class "Default")
      (node (ref "AB2") (pin "6") (pinfunction "6_6") (pintype "passive"))
      (node (ref "C5") (pin "2") (pinfunction "2_2") (pintype "passive"))
      (node (ref "C6") (pin "2") (pinfunction "2_2") (pintype "passive"))
      (node (ref "C8") (pin "2") (pinfunction "2_2") (pintype "passive"))
      (node (ref "R16") (pin "2") (pinfunction "2_2") (pintype "passive"))
      (node (ref "U$10") (pin "6") (pinfunction "VSS_6") (pintype "bidirectional"))
      (node (ref "U$12") (pin "3") (pinfunction "VSS_3") (pintype "bidirectional"))
      (node (ref "U$14") (pin "2") (pinfunction "S_2") (pintype "bidirectional"))
    )
    (net (code "8") (name "/B-4") (class "Default")
      (node (ref "AB2") (pin "1") (pinfunction "1_1") (pintype "passive"))
      (node (ref "C21") (pin "2") (pinfunction "2_2") (pintype "passive"))
      (node (ref "C22") (pin "2") (pinfunction "2_2") (pintype "passive"))
      (node (ref "C24") (pin "2") (pinfunction "2_2") (pintype "passive"))
      (node (ref "R48") (pin "2") (pinfunction "2_2") (pintype "passive"))
      (node (ref "U$38") (pin "6") (pinfunction "VSS_6") (pintype "bidirectional"))
      (node (ref "U$40") (pin "3") (pinfunction "VSS_3") (pintype "bidirectional"))
      (node (ref "U$42") (pin "2") (pinfunction "S_2") (pintype "bidirectional"))
    )
    (net (code "9") (name "/B-5") (class "Default")
      (node (ref "AB3") (pin "6") (pinfunction "6_6") (pintype "passive"))
      (node (ref "C10") (pin "2") (pinfunction "2_2") (pintype "passive"))
      (node (ref "C12") (pin "2") (pinfunction "2_2") (pintype "passive"))
      (node (ref "C9") (pin "2") (pinfunction "2_2") (pintype "passive"))
      (node (ref "R24") (pin "2") (pinfunction "2_2") (pintype "passive"))
      (node (ref "U$17") (pin "6") (pinfunction "VSS_6") (pintype "bidirectional"))
      (node (ref "U$19") (pin "3") (pinfunction "VSS_3") (pintype "bidirectional"))
      (node (ref "U$21") (pin "2") (pinfunction "S_2") (pintype "bidirectional"))
    )
    (net (code "10") (name "/B-6") (class "Default")
      (node (ref "AB3") (pin "1") (pinfunction "1_1") (pintype "passive"))
      (node (ref "C17") (pin "2") (pinfunction "2_2") (pintype "passive"))
      (node (ref "C18") (pin "2") (pinfunction "2_2") (pintype "passive"))
      (node (ref "C20") (pin "2") (pinfunction "2_2") (pintype "passive"))
      (node (ref "R40") (pin "2") (pinfunction "2_2") (pintype "passive"))
      (node (ref "U$31") (pin "6") (pinfunction "VSS_6") (pintype "bidirectional"))
      (node (ref "U$33") (pin "3") (pinfunction "VSS_3") (pintype "bidirectional"))
      (node (ref "U$35") (pin "2") (pinfunction "S_2") (pintype "bidirectional"))
    )
    (net (code "11") (name "/BMS+") (class "Default")
      (node (ref "AB1") (pin "8") (pinfunction "8_8") (pintype "passive"))
      (node (ref "AB2") (pin "8") (pinfunction "8_8") (pintype "passive"))
      (node (ref "AB3") (pin "8") (pinfunction "8_8") (pintype "passive"))
      (node (ref "R10") (pin "2") (pinfunction "2_2") (pintype "passive"))
      (node (ref "R12") (pin "2") (pinfunction "2_2") (pintype "passive"))
      (node (ref "R14") (pin "2") (pinfunction "2_2") (pintype "passive"))
      (node (ref "R18") (pin "2") (pinfunction "2_2") (pintype "passive"))
      (node (ref "R2") (pin "2") (pinfunction "2_2") (pintype "passive"))
      (node (ref "R20") (pin "2") (pinfunction "2_2") (pintype "passive"))
      (node (ref "R22") (pin "2") (pinfunction "2_2") (pintype "passive"))
      (node (ref "R34") (pin "2") (pinfunction "2_2") (pintype "passive"))
      (node (ref "R36") (pin "2") (pinfunction "2_2") (pintype "passive"))
      (node (ref "R38") (pin "2") (pinfunction "2_2") (pintype "passive"))
      (node (ref "R4") (pin "2") (pinfunction "2_2") (pintype "passive"))
      (node (ref "R42") (pin "2") (pinfunction "2_2") (pintype "passive"))
      (node (ref "R44") (pin "2") (pinfunction "2_2") (pintype "passive"))
      (node (ref "R46") (pin "2") (pinfunction "2_2") (pintype "passive"))
      (node (ref "R50") (pin "2") (pinfunction "2_2") (pintype "passive"))
      (node (ref "R52") (pin "2") (pinfunction "2_2") (pintype "passive"))
      (node (ref "R54") (pin "2") (pinfunction "2_2") (pintype "passive"))
      (node (ref "R6") (pin "2") (pinfunction "2_2") (pintype "passive"))
      (node (ref "R75") (pin "2") (pinfunction "2_2") (pintype "passive"))
      (node (ref "R76") (pin "1") (pinfunction "1_1") (pintype "passive"))
    )
    (net (code "12") (name "/BMS1") (class "Default")
      (node (ref "IC2") (pin "15") (pinfunction "PA5_15") (pintype "bidirectional"))
      (node (ref "R94") (pin "1") (pinfunction "1_1") (pintype "passive"))
      (node (ref "R95") (pin "1") (pinfunction "1_1") (pintype "passive"))
    )
    (net (code "13") (name "/BMS2") (class "Default")
      (node (ref "IC2") (pin "16") (pinfunction "PA6_16") (pintype "bidirectional"))
      (node (ref "R98") (pin "1") (pinfunction "1_1") (pintype "passive"))
      (node (ref "R99") (pin "1") (pinfunction "1_1") (pintype "passive"))
    )
    (net (code "14") (name "/BMS3") (class "Default")
      (node (ref "IC2") (pin "13") (pinfunction "PA3_13") (pintype "bidirectional"))
      (node (ref "R92") (pin "1") (pinfunction "1_1") (pintype "passive"))
      (node (ref "R93") (pin "1") (pinfunction "1_1") (pintype "passive"))
    )
    (net (code "15") (name "/BMS4") (class "Default")
      (node (ref "IC2") (pin "14") (pinfunction "PA4_14") (pintype "bidirectional"))
      (node (ref "R96") (pin "1") (pinfunction "1_1") (pintype "passive"))
      (node (ref "R97") (pin "1") (pinfunction "1_1") (pintype "passive"))
    )
    (net (code "16") (name "/BMS5") (class "Default")
      (node (ref "IC2") (pin "11") (pinfunction "PA1_11") (pintype "bidirectional"))
      (node (ref "R90") (pin "1") (pinfunction "1_1") (pintype "passive"))
      (node (ref "R91") (pin "1") (pinfunction "1_1") (pintype "passive"))
    )
    (net (code "17") (name "/BMS6") (class "Default")
      (node (ref "IC2") (pin "12") (pinfunction "PA2_12") (pintype "bidirectional"))
      (node (ref "R88") (pin "1") (pinfunction "1_1") (pintype "passive"))
      (node (ref "R89") (pin "1") (pinfunction "1_1") (pintype "passive"))
    )
    (net (code "18") (name "/BUS+") (class "Default")
      (node (ref "R71") (pin "2") (pinfunction "2_2") (pintype "passive"))
      (node (ref "R73") (pin "1") (pinfunction "1_1") (pintype "passive"))
      (node (ref "S1") (pin "2") (pinfunction "P_2") (pintype "passive"))
    )
    (net (code "19") (name "/BUSPLUS") (class "Default")
      (node (ref "BSK4") (pin "7") (pinfunction "7_7") (pintype "passive"))
      (node (ref "S1") (pin "1") (pinfunction "O_1") (pintype "passive"))
    )
    (net (code "20") (name "/DPD_RST") (class "Default")
      (node (ref "AD5272#2") (pin "7") (pinfunction "RESET_7") (pintype "bidirectional"))
      (node (ref "IC2") (pin "28") (pinfunction "PB15_28") (pintype "bidirectional"))
    )
    (net (code "21") (name "/GND") (class "Default")
      (node (ref "AB1") (pin "4") (pinfunction "4_4") (pintype "passive"))
      (node (ref "AB2") (pin "4") (pinfunction "4_4") (pintype "passive"))
      (node (ref "AB3") (pin "4") (pinfunction "4_4") (pintype "passive"))
      (node (ref "AD5272#2") (pin "10") (pinfunction "ADDR_10") (pintype "bidirectional"))
      (node (ref "AD5272#2") (pin "6") (pinfunction "GND_6") (pintype "bidirectional"))
      (node (ref "BSK4") (pin "1") (pinfunction "1_1") (pintype "passive"))
      (node (ref "C15") (pin "2") (pinfunction "2_2") (pintype "passive"))
      (node (ref "C16") (pin "2") (pinfunction "2_2") (pintype "passive"))
      (node (ref "C30") (pin "2") (pinfunction "2_2") (pintype "passive"))
      (node (ref "C31") (pin "2") (pinfunction "2_2") (pintype "passive"))
      (node (ref "C35") (pin "P$2") (pinfunction "2_P$2") (pintype "passive"))
      (node (ref "C36") (pin "2") (pinfunction "2_2") (pintype "passive"))
      (node (ref "C37") (pin "P$2") (pinfunction "2_P$2") (pintype "passive"))
      (node (ref "C38") (pin "2") (pinfunction "2_2") (pintype "passive"))
      (node (ref "C39") (pin "2") (pinfunction "2_2") (pintype "passive"))
      (node (ref "C44") (pin "2") (pinfunction "2_2") (pintype "passive"))
      (node (ref "C45") (pin "2") (pinfunction "2_2") (pintype "passive"))
      (node (ref "C46") (pin "2") (pinfunction "2_2") (pintype "passive"))
      (node (ref "C47") (pin "2") (pinfunction "2_2") (pintype "passive"))
      (node (ref "C48") (pin "2") (pinfunction "2_2") (pintype "passive"))
      (node (ref "C49") (pin "P$2") (pinfunction "2_P$2") (pintype "passive"))
      (node (ref "C50") (pin "P$2") (pinfunction "2_P$2") (pintype "passive"))
      (node (ref "C51") (pin "2") (pinfunction "2_2") (pintype "passive"))
      (node (ref "C52") (pin "2") (pinfunction "2_2") (pintype "passive"))
      (node (ref "C53") (pin "2") (pinfunction "2_2") (pintype "passive"))
      (node (ref "C54") (pin "2") (pinfunction "2_2") (pintype "passive"))
      (node (ref "C55") (pin "2") (pinfunction "2_2") (pintype "passive"))
      (node (ref "IC2") (pin "20") (pinfunction "PB2_20") (pintype "bidirectional"))
      (node (ref "IC2") (pin "23") (pinfunction "VSSA_23") (pintype "power_in"))
      (node (ref "IC2") (pin "35") (pinfunction "VSSA_35") (pintype "power_in"))
      (node (ref "IC2") (pin "44") (pinfunction "BOOT0_44") (pintype "input"))
      (node (ref "IC2") (pin "47") (pinfunction "VSSA_47") (pintype "power_in"))
      (node (ref "IC2") (pin "8") (pinfunction "VSSA_8") (pintype "power_in"))
      (node (ref "INA219#1") (pin "3") (pinfunction "GND_3") (pintype "bidirectional"))
      (node (ref "INA219#1") (pin "7") (pinfunction "A0_7") (pintype "bidirectional"))
      (node (ref "INA219#1") (pin "8") (pinfunction "A1_8") (pintype "bidirectional"))
      (node (ref "MICRO") (pin "GND") (pinfunction "5_GND") (pintype "passive"))
      (node (ref "MICRO") (pin "Z1") (pinfunction "5_Z1") (pintype "passive"))
      (node (ref "MICRO") (pin "Z2") (pinfunction "5_Z2") (pintype "passive"))
      (node (ref "MICRO") (pin "Z3") (pinfunction "5_Z3") (pintype "passive"))
      (node (ref "MICRO") (pin "Z4") (pinfunction "5_Z4") (pintype "passive"))
      (node (ref "R100") (pin "1") (pinfunction "1_1") (pintype "passive"))
      (node (ref "R28") (pin "1") (pinfunction "1_1") (pintype "passive"))
      (node (ref "R30") (pin "2") (pinfunction "2_2") (pintype "passive"))
      (node (ref "R31") (pin "1") (pinfunction "1_1") (pintype "passive"))
      (node (ref "R32") (pin "1") (pinfunction "1_1") (pintype "passive"))
      (node (ref "R57") (pin "1") (pinfunction "1_1") (pintype "passive"))
      (node (ref "R62") (pin "1") (pinfunction "1_1") (pintype "passive"))
      (node (ref "R67") (pin "1") (pinfunction "1_1") (pintype "passive"))
      (node (ref "R68") (pin "1") (pinfunction "1_1") (pintype "passive"))
      (node (ref "R70") (pin "2") (pinfunction "2_2") (pintype "passive"))
      (node (ref "R82") (pin "1") (pinfunction "1_1") (pintype "passive"))
      (node (ref "U$16") (pin "14") (pinfunction "SGND_14") (pintype "bidirectional"))
      (node (ref "U$16") (pin "20") (pinfunction "PGND_20") (pintype "bidirectional"))
      (node (ref "U$16") (pin "25") (pinfunction "PGND_25") (pintype "bidirectional"))
      (node (ref "U$16") (pin "28") (pinfunction "PWM_28") (pintype "bidirectional"))
      (node (ref "U$16") (pin "29") (pinfunction "PGND_29") (pintype "bidirectional"))
      (node (ref "U$16") (pin "4") (pinfunction "PGND_4") (pintype "bidirectional"))
      (node (ref "U$16") (pin "9") (pinfunction "PGND_9") (pintype "bidirectional"))
      (node (ref "U$2") (pin "P$3") (pinfunction "GND_P$3") (pintype "bidirectional"))
      (node (ref "U$22") (pin "23") (pinfunction "S1_23") (pintype "bidirectional"))
      (node (ref "U$23") (pin "GND0") (pinfunction "GND_GND0") (pintype "bidirectional"))
      (node (ref "U$23") (pin "GND1") (pinfunction "GND_GND1") (pintype "bidirectional"))
      (node (ref "U$27") (pin "23") (pinfunction "S1_23") (pintype "bidirectional"))
      (node (ref "U$28") (pin "23") (pinfunction "S1_23") (pintype "bidirectional"))
      (node (ref "U$29") (pin "23") (pinfunction "S1_23") (pintype "bidirectional"))
      (node (ref "U$30") (pin "23") (pinfunction "S1_23") (pintype "bidirectional"))
      (node (ref "U$57") (pin "3") (pinfunction "GND_3") (pintype "bidirectional"))
      (node (ref "U$57") (pin "8") (pinfunction "A1_8") (pintype "bidirectional"))
      (node (ref "U$59") (pin "14") (pinfunction "SGND_14") (pintype "bidirectional"))
      (node (ref "U$59") (pin "20") (pinfunction "PGND_20") (pintype "bidirectional"))
      (node (ref "U$59") (pin "25") (pinfunction "PGND_25") (pintype "bidirectional"))
      (node (ref "U$59") (pin "28") (pinfunction "PWM_28") (pintype "bidirectional"))
      (node (ref "U$59") (pin "29") (pinfunction "PGND_29") (pintype "bidirectional"))
      (node (ref "U$59") (pin "4") (pinfunction "PGND_4") (pintype "bidirectional"))
      (node (ref "U$59") (pin "9") (pinfunction "PGND_9") (pintype "bidirectional"))
      (node (ref "U$9") (pin "23") (pinfunction "S1_23") (pintype "bidirectional"))
    )
    (net (code "22") (name "/I2CINT") (class "Default")
      (node (ref "BSK4") (pin "3") (pinfunction "3_3") (pintype "passive"))
      (node (ref "IC2") (pin "43") (pinfunction "PB7_43") (pintype "bidirectional"))
    )
    (net (code "23") (name "/INA_BMS+") (class "Default")
      (node (ref "C35") (pin "P$1") (pinfunction "1_P$1") (pintype "passive"))
      (node (ref "C50") (pin "P$1") (pinfunction "1_P$1") (pintype "passive"))
      (node (ref "R72") (pin "2") (pinfunction "2_2") (pintype "passive"))
      (node (ref "R75") (pin "1") (pinfunction "1_1") (pintype "passive"))
      (node (ref "R77") (pin "1") (pinfunction "1_1") (pintype "passive"))
      (node (ref "U$16") (pin "19") (pinfunction "VIN_19") (pintype "bidirectional"))
      (node (ref "U$16") (pin "22") (pinfunction "PVIN_22") (pintype "bidirectional"))
      (node (ref "U$16") (pin "23") (pinfunction "PVIN_23") (pintype "bidirectional"))
      (node (ref "U$59") (pin "6") (pinfunction "PVOUT_6") (pintype "bidirectional"))
      (node (ref "U$59") (pin "7") (pinfunction "PVOUT_7") (pintype "bidirectional"))
    )
    (net (code "24") (name "/INA_BUS+") (class "Default")
      (node (ref "C37") (pin "P$1") (pinfunction "1_P$1") (pintype "passive"))
      (node (ref "C49") (pin "P$1") (pinfunction "1_P$1") (pintype "passive"))
      (node (ref "R61") (pin "2") (pinfunction "2_2") (pintype "passive"))
      (node (ref "R65") (pin "2") (pinfunction "2_2") (pintype "passive"))
      (node (ref "R71") (pin "1") (pinfunction "1_1") (pintype "passive"))
      (node (ref "R74") (pin "1") (pinfunction "1_1") (pintype "passive"))
      (node (ref "R87") (pin "2") (pinfunction "2_2") (pintype "passive"))
      (node (ref "U$16") (pin "6") (pinfunction "PVOUT_6") (pintype "bidirectional"))
      (node (ref "U$16") (pin "7") (pinfunction "PVOUT_7") (pintype "bidirectional"))
      (node (ref "U$59") (pin "19") (pinfunction "VIN_19") (pintype "bidirectional"))
      (node (ref "U$59") (pin "22") (pinfunction "PVIN_22") (pintype "bidirectional"))
      (node (ref "U$59") (pin "23") (pinfunction "PVIN_23") (pintype "bidirectional"))
    )
    (net (code "25") (name "/N$47") (class "Default")
      (node (ref "AD5272#2") (pin "1") (pinfunction "VDD_1") (pintype "bidirectional"))
      (node (ref "C31") (pin "1") (pinfunction "1_1") (pintype "passive"))
      (node (ref "C51") (pin "1") (pinfunction "1_1") (pintype "passive"))
      (node (ref "C52") (pin "1") (pinfunction "1_1") (pintype "passive"))
      (node (ref "LED1") (pin "A") (pinfunction "A_A") (pintype "passive"))
      (node (ref "U$16") (pin "11") (pinfunction "SVCC_11") (pintype "bidirectional"))
      (node (ref "U$16") (pin "15") (pinfunction "MPPC_15") (pintype "bidirectional"))
      (node (ref "U$16") (pin "16") (pinfunction "VCC_16") (pintype "bidirectional"))
    )
    (net (code "26") (name "/NRST") (class "Default")
      (node (ref "IC2") (pin "7") (pinfunction "NRST_7") (pintype "bidirectional"))
      (node (ref "R79") (pin "2") (pinfunction "2_2") (pintype "passive"))
      (node (ref "U$23") (pin "NRST/EN") (pinfunction "NRST/EN_NRST/EN") (pintype "bidirectional"))
    )
    (net (code "27") (name "/OC1") (class "Default")
      (node (ref "U$26") (pin "5") (pinfunction "G2_5") (pintype "bidirectional"))
      (node (ref "U$3") (pin "2") (pinfunction "OC_2") (pintype "bidirectional"))
    )
    (net (code "28") (name "/OC2") (class "Default")
      (node (ref "U$1") (pin "5") (pinfunction "G2_5") (pintype "bidirectional"))
      (node (ref "U$45") (pin "2") (pinfunction "OC_2") (pintype "bidirectional"))
    )
    (net (code "29") (name "/OC3") (class "Default")
      (node (ref "U$10") (pin "2") (pinfunction "OC_2") (pintype "bidirectional"))
      (node (ref "U$25") (pin "5") (pinfunction "G2_5") (pintype "bidirectional"))
    )
    (net (code "30") (name "/OC4") (class "Default")
      (node (ref "U$38") (pin "2") (pinfunction "OC_2") (pintype "bidirectional"))
      (node (ref "U$8") (pin "5") (pinfunction "G2_5") (pintype "bidirectional"))
    )
    (net (code "31") (name "/OC5") (class "Default")
      (node (ref "U$17") (pin "2") (pinfunction "OC_2") (pintype "bidirectional"))
      (node (ref "U$24") (pin "5") (pinfunction "G2_5") (pintype "bidirectional"))
    )
    (net (code "32") (name "/OC6") (class "Default")
      (node (ref "U$15") (pin "5") (pinfunction "G2_5") (pintype "bidirectional"))
      (node (ref "U$31") (pin "2") (pinfunction "OC_2") (pintype "bidirectional"))
    )
    (net (code "33") (name "/OD1") (class "Default")
      (node (ref "U$26") (pin "4") (pinfunction "G1_4") (pintype "bidirectional"))
      (node (ref "U$3") (pin "1") (pinfunction "OD_1") (pintype "bidirectional"))
    )
    (net (code "34") (name "/OD2") (class "Default")
      (node (ref "U$1") (pin "4") (pinfunction "G1_4") (pintype "bidirectional"))
      (node (ref "U$45") (pin "1") (pinfunction "OD_1") (pintype "bidirectional"))
    )
    (net (code "35") (name "/OD3") (class "Default")
      (node (ref "U$10") (pin "1") (pinfunction "OD_1") (pintype "bidirectional"))
      (node (ref "U$25") (pin "4") (pinfunction "G1_4") (pintype "bidirectional"))
    )
    (net (code "36") (name "/OD4") (class "Default")
      (node (ref "U$38") (pin "1") (pinfunction "OD_1") (pintype "bidirectional"))
      (node (ref "U$8") (pin "4") (pinfunction "G1_4") (pintype "bidirectional"))
    )
    (net (code "37") (name "/OD5") (class "Default")
      (node (ref "U$17") (pin "1") (pinfunction "OD_1") (pintype "bidirectional"))
      (node (ref "U$24") (pin "4") (pinfunction "G1_4") (pintype "bidirectional"))
    )
    (net (code "38") (name "/OD6") (class "Default")
      (node (ref "U$15") (pin "4") (pinfunction "G1_4") (pintype "bidirectional"))
      (node (ref "U$31") (pin "1") (pinfunction "OD_1") (pintype "bidirectional"))
    )
    (net (code "39") (name "/PGOOD1") (class "Default")
      (node (ref "IC2") (pin "18") (pinfunction "PB0_18") (pintype "bidirectional"))
      (node (ref "LED2") (pin "A") (pinfunction "A_A") (pintype "passive"))
      (node (ref "U$59") (pin "10") (pinfunction "PGOOD_10") (pintype "bidirectional"))
    )
    (net (code "40") (name "/PGOOD2") (class "Default")
      (node (ref "IC2") (pin "19") (pinfunction "PB1_19") (pintype "bidirectional"))
      (node (ref "LED3") (pin "A") (pinfunction "A_A") (pintype "passive"))
      (node (ref "U$16") (pin "10") (pinfunction "PGOOD_10") (pintype "bidirectional"))
    )
    (net (code "41") (name "/RX-C") (class "Default")
      (node (ref "IC2") (pin "31") (pinfunction "PA10_31") (pintype "bidirectional"))
      (node (ref "U$23") (pin "RX0") (pinfunction "RX0_RX0") (pintype "bidirectional"))
    )
    (net (code "42") (name "/SCL") (class "Default")
      (node (ref "AD5272#2") (pin "9") (pinfunction "SCL_9") (pintype "bidirectional"))
      (node (ref "IC2") (pin "21") (pinfunction "PB10_21") (pintype "bidirectional"))
      (node (ref "INA219#1") (pin "5") (pinfunction "SCL_5") (pintype "bidirectional"))
      (node (ref "R101") (pin "2") (pinfunction "2_2") (pintype "passive"))
      (node (ref "U$57") (pin "5") (pinfunction "SCL_5") (pintype "bidirectional"))
    )
    (net (code "43") (name "/SCLTM") (class "Default")
      (node (ref "BSK4") (pin "5") (pinfunction "5_5") (pintype "passive"))
      (node (ref "IC2") (pin "45") (pinfunction "PB8_45") (pintype "bidirectional"))
      (node (ref "R25") (pin "2") (pinfunction "2_2") (pintype "passive"))
    )
    (net (code "44") (name "/SDA") (class "Default")
      (node (ref "AD5272#2") (pin "8") (pinfunction "SDA_8") (pintype "bidirectional"))
      (node (ref "IC2") (pin "22") (pinfunction "PB11_22") (pintype "bidirectional"))
      (node (ref "INA219#1") (pin "6") (pinfunction "SDA_6") (pintype "bidirectional"))
      (node (ref "R102") (pin "2") (pinfunction "2_2") (pintype "passive"))
      (node (ref "U$57") (pin "6") (pinfunction "SDA_6") (pintype "bidirectional"))
    )
    (net (code "45") (name "/SDATM") (class "Default")
      (node (ref "BSK4") (pin "4") (pinfunction "4_4") (pintype "passive"))
      (node (ref "IC2") (pin "46") (pinfunction "PB9_46") (pintype "bidirectional"))
      (node (ref "R26") (pin "2") (pinfunction "2_2") (pintype "passive"))
    )
    (net (code "46") (name "/SWC") (class "Default")
      (node (ref "IC2") (pin "37") (pinfunction "PA14_37") (pintype "bidirectional"))
      (node (ref "R27") (pin "2") (pinfunction "2_2") (pintype "passive"))
      (node (ref "U$23") (pin "SWC/TXD") (pinfunction "SWC/TXD_SWC/TXD") (pintype "bidirectional"))
    )
    (net (code "47") (name "/SWD") (class "Default")
      (node (ref "IC2") (pin "34") (pinfunction "PA13_34") (pintype "bidirectional"))
      (node (ref "R64") (pin "2") (pinfunction "2_2") (pintype "passive"))
      (node (ref "U$23") (pin "SWD/RXD") (pinfunction "SWD/RXD_SWD/RXD") (pintype "bidirectional"))
    )
    (net (code "48") (name "/TIME") (class "Default")
      (node (ref "BSK4") (pin "2") (pinfunction "2_2") (pintype "passive"))
      (node (ref "IC2") (pin "42") (pinfunction "PB6_42") (pintype "bidirectional"))
    )
    (net (code "49") (name "/TX-C") (class "Default")
      (node (ref "IC2") (pin "30") (pinfunction "PA9_30") (pintype "bidirectional"))
      (node (ref "U$23") (pin "TX0") (pinfunction "TX0_TX0") (pintype "bidirectional"))
    )
    (net (code "50") (name "/VDD") (class "Default")
      (node (ref "AB1") (pin "3") (pinfunction "3_3") (pintype "passive"))
      (node (ref "AB2") (pin "3") (pinfunction "3_3") (pintype "passive"))
      (node (ref "AB3") (pin "3") (pinfunction "3_3") (pintype "passive"))
      (node (ref "BSK4") (pin "6") (pinfunction "6_6") (pintype "passive"))
      (node (ref "C15") (pin "1") (pinfunction "1_1") (pintype "passive"))
      (node (ref "C16") (pin "1") (pinfunction "1_1") (pintype "passive"))
      (node (ref "C48") (pin "1") (pinfunction "1_1") (pintype "passive"))
      (node (ref "C53") (pin "1") (pinfunction "1_1") (pintype "passive"))
      (node (ref "C54") (pin "1") (pinfunction "1_1") (pintype "passive"))
      (node (ref "C55") (pin "1") (pinfunction "1_1") (pintype "passive"))
      (node (ref "IC2") (pin "1") (pinfunction "VBAT_1") (pintype "power_in"))
      (node (ref "IC2") (pin "24") (pinfunction "VDDA_24") (pintype "power_in"))
      (node (ref "IC2") (pin "36") (pinfunction "VDDA_36") (pintype "power_in"))
      (node (ref "IC2") (pin "48") (pinfunction "VDDA_48") (pintype "power_in"))
      (node (ref "IC2") (pin "9") (pinfunction "VDDA_9") (pintype "power_in"))
      (node (ref "INA219#1") (pin "4") (pinfunction "VS_4") (pintype "bidirectional"))
      (node (ref "PB5") (pin "A") (pinfunction "A_A") (pintype "passive"))
      (node (ref "PWR") (pin "A") (pinfunction "A_A") (pintype "passive"))
      (node (ref "R101") (pin "1") (pinfunction "1_1") (pintype "passive"))
      (node (ref "R102") (pin "1") (pinfunction "1_1") (pintype "passive"))
      (node (ref "R25") (pin "1") (pinfunction "1_1") (pintype "passive"))
      (node (ref "R26") (pin "1") (pinfunction "1_1") (pintype "passive"))
      (node (ref "R27") (pin "1") (pinfunction "1_1") (pintype "passive"))
      (node (ref "R64") (pin "1") (pinfunction "1_1") (pintype "passive"))
      (node (ref "R79") (pin "1") (pinfunction "1_1") (pintype "passive"))
      (node (ref "U$2") (pin "P$5") (pinfunction "VCC_P$5") (pintype "bidirectional"))
      (node (ref "U$23") (pin "3V3/BUS0") (pinfunction "3V3/BUS_3V3/BUS0") (pintype "bidirectional"))
      (node (ref "U$23") (pin "3V3/BUS1") (pinfunction "3V3/BUS_3V3/BUS1") (pintype "bidirectional"))
      (node (ref "U$57") (pin "4") (pinfunction "VS_4") (pintype "bidirectional"))
      (node (ref "U$57") (pin "7") (pinfunction "A0_7") (pintype "bidirectional"))
    )
    (net (code "51") (name "/Y") (class "Default")
      (node (ref "U$16") (pin "18") (pinfunction "RUN_18") (pintype "bidirectional"))
      (node (ref "U$2") (pin "P$4") (pinfunction "Y_P$4") (pintype "bidirectional"))
    )
    (net (code "52") (name "Net-(3,3µH-Pad1)") (class "Default")
      (node (ref "3,3µH") (pin "1") (pinfunction "1_1") (pintype "bidirectional"))
      (node (ref "C34") (pin "1") (pinfunction "1_1") (pintype "passive"))
      (node (ref "U$59") (pin "5") (pinfunction "SW2_5") (pintype "bidirectional"))
      (node (ref "U$59") (pin "8") (pinfunction "SW2_8") (pintype "bidirectional"))
    )
    (net (code "53") (name "Net-(3,3µH-Pad2)") (class "Default")
      (node (ref "3,3µH") (pin "2") (pinfunction "2_2") (pintype "bidirectional"))
      (node (ref "C33") (pin "1") (pinfunction "1_1") (pintype "passive"))
      (node (ref "U$59") (pin "21") (pinfunction "SW1_21") (pintype "bidirectional"))
      (node (ref "U$59") (pin "24") (pinfunction "SW1_24") (pintype "bidirectional"))
    )
    (net (code "54") (name "Net-(3,3µH1-Pad1)") (class "Default")
      (node (ref "3,3µH1") (pin "1") (pinfunction "1_1") (pintype "bidirectional"))
      (node (ref "C14") (pin "1") (pinfunction "1_1") (pintype "passive"))
      (node (ref "U$16") (pin "5") (pinfunction "SW2_5") (pintype "bidirectional"))
      (node (ref "U$16") (pin "8") (pinfunction "SW2_8") (pintype "bidirectional"))
    )
    (net (code "55") (name "Net-(3,3µH1-Pad2)") (class "Default")
      (node (ref "3,3µH1") (pin "2") (pinfunction "2_2") (pintype "bidirectional"))
      (node (ref "C13") (pin "1") (pinfunction "1_1") (pintype "passive"))
      (node (ref "U$16") (pin "21") (pinfunction "SW1_21") (pintype "bidirectional"))
      (node (ref "U$16") (pin "24") (pinfunction "SW1_24") (pintype "bidirectional"))
    )
    (net (code "56") (name "Net-(AD5272#2-A)") (class "Default")
      (node (ref "AD5272#2") (pin "2") (pinfunction "A_2") (pintype "bidirectional"))
      (node (ref "R61") (pin "1") (pinfunction "1_1") (pintype "passive"))
      (node (ref "U$16") (pin "12") (pinfunction "FB_12") (pintype "bidirectional"))
    )
    (net (code "57") (name "Net-(AD5272#2-CAP)") (class "Default")
      (node (ref "AD5272#2") (pin "5") (pinfunction "CAP_5") (pintype "bidirectional"))
      (node (ref "C29") (pin "1") (pinfunction "1_1") (pintype "passive"))
    )
    (net (code "58") (name "Net-(AD5272#2-VSS)") (class "Default")
      (node (ref "AD5272#2") (pin "3") (pinfunction "W_3") (pintype "bidirectional"))
      (node (ref "AD5272#2") (pin "4") (pinfunction "VSS_4") (pintype "bidirectional"))
      (node (ref "C29") (pin "2") (pinfunction "2_2") (pintype "passive"))
      (node (ref "R30") (pin "1") (pinfunction "1_1") (pintype "passive"))
    )
    (net (code "59") (name "Net-(C005R-1)") (class "Default")
      (node (ref "C005R") (pin "P$1") (pinfunction "1_P$1") (pintype "passive"))
      (node (ref "C46") (pin "1") (pinfunction "1_1") (pintype "passive"))
      (node (ref "IC2") (pin "3") (pinfunction "PC14_3") (pintype "bidirectional"))
    )
    (net (code "60") (name "Net-(C005R-2)") (class "Default")
      (node (ref "C005R") (pin "P$2") (pinfunction "2_P$2") (pintype "passive"))
      (node (ref "C47") (pin "1") (pinfunction "1_1") (pintype "passive"))
      (node (ref "IC2") (pin "4") (pinfunction "PC15_4") (pintype "bidirectional"))
    )
    (net (code "61") (name "Net-(C30-Pad1)") (class "Default")
      (node (ref "C30") (pin "1") (pinfunction "1_1") (pintype "passive"))
      (node (ref "R29") (pin "2") (pinfunction "2_2") (pintype "passive"))
    )
    (net (code "62") (name "Net-(C36-Pad1)") (class "Default")
      (node (ref "C36") (pin "1") (pinfunction "1_1") (pintype "passive"))
      (node (ref "R69") (pin "2") (pinfunction "2_2") (pintype "passive"))
    )
    (net (code "63") (name "Net-(C38-Pad1)") (class "Default")
      (node (ref "C38") (pin "1") (pinfunction "1_1") (pintype "passive"))
      (node (ref "R66") (pin "1") (pinfunction "1_1") (pintype "passive"))
    )
    (net (code "64") (name "Net-(IC2-OSC_IN)") (class "Default")
      (node (ref "C45") (pin "1") (pinfunction "1_1") (pintype "passive"))
      (node (ref "IC2") (pin "5") (pinfunction "OSC_IN_5") (pintype "bidirectional"))
      (node (ref "Q5") (pin "2") (pinfunction "2_2") (pintype "passive"))
      (node (ref "R78") (pin "2") (pinfunction "2_2") (pintype "passive"))
    )
    (net (code "65") (name "Net-(IC2-OSC_OUT)") (class "Default")
      (node (ref "C44") (pin "1") (pinfunction "1_1") (pintype "passive"))
      (node (ref "IC2") (pin "6") (pinfunction "OSC_OUT_6") (pintype "bidirectional"))
      (node (ref "Q5") (pin "1") (pinfunction "1_1") (pintype "passive"))
      (node (ref "R78") (pin "1") (pinfunction "1_1") (pintype "passive"))
    )
    (net (code "66") (name "Net-(IC2-PB5)") (class "Default")
      (node (ref "IC2") (pin "41") (pinfunction "PB5_41") (pintype "bidirectional"))
      (node (ref "R81") (pin "1") (pinfunction "1_1") (pintype "passive"))
    )
    (net (code "67") (name "Net-(INA219#1-IN+)") (class "Default")
      (node (ref "C40") (pin "1") (pinfunction "1_1") (pintype "passive"))
      (node (ref "INA219#1") (pin "1") (pinfunction "IN+_1") (pintype "bidirectional"))
      (node (ref "R73") (pin "2") (pinfunction "2_2") (pintype "passive"))
    )
    (net (code "68") (name "Net-(INA219#1-IN-)") (class "Default")
      (node (ref "C40") (pin "2") (pinfunction "2_2") (pintype "passive"))
      (node (ref "INA219#1") (pin "2") (pinfunction "IN-_2") (pintype "bidirectional"))
      (node (ref "R74") (pin "2") (pinfunction "2_2") (pintype "passive"))
    )
    (net (code "69") (name "Net-(LED1-PadC)") (class "Default")
      (node (ref "LED1") (pin "C") (pinfunction "C_C") (pintype "passive"))
      (node (ref "R31") (pin "2") (pinfunction "2_2") (pintype "passive"))
    )
    (net (code "70") (name "Net-(LED2-PadC)") (class "Default")
      (node (ref "LED2") (pin "C") (pinfunction "C_C") (pintype "passive"))
      (node (ref "R32") (pin "2") (pinfunction "2_2") (pintype "passive"))
    )
    (net (code "71") (name "Net-(LED3-PadC)") (class "Default")
      (node (ref "LED3") (pin "C") (pinfunction "C_C") (pintype "passive"))
      (node (ref "R57") (pin "2") (pinfunction "2_2") (pintype "passive"))
    )
    (net (code "72") (name "Net-(LED8-PadC)") (class "Default")
      (node (ref "LED8") (pin "C") (pinfunction "C_C") (pintype "passive"))
      (node (ref "R100") (pin "2") (pinfunction "2_2") (pintype "passive"))
    )
    (net (code "73") (name "Net-(PB5-PadC)") (class "Default")
      (node (ref "PB5") (pin "C") (pinfunction "C_C") (pintype "passive"))
      (node (ref "R81") (pin "2") (pinfunction "2_2") (pintype "passive"))
    )
    (net (code "74") (name "Net-(PWR-PadC)") (class "Default")
      (node (ref "PWR") (pin "C") (pinfunction "C_C") (pintype "passive"))
      (node (ref "R82") (pin "2") (pinfunction "2_2") (pintype "passive"))
    )
    (net (code "75") (name "Net-(U$1-S1)") (class "Default")
      (node (ref "U$1") (pin "23") (pinfunction "S1_23") (pintype "bidirectional"))
      (node (ref "U$30") (pin "67") (pinfunction "S2_67") (pintype "bidirectional"))
    )
    (net (code "76") (name "Net-(U$1-S2)") (class "Default")
      (node (ref "R49") (pin "2") (pinfunction "2_2") (pintype "passive"))
      (node (ref "R56") (pin "1") (pinfunction "1_1") (pintype "passive"))
      (node (ref "U$1") (pin "67") (pinfunction "S2_67") (pintype "bidirectional"))
    )
    (net (code "77") (name "Net-(U$3-CS)") (class "Default")
      (node (ref "R1") (pin "1") (pinfunction "1_1") (pintype "passive"))
      (node (ref "U$3") (pin "3") (pinfunction "CS_3") (pintype "bidirectional"))
    )
    (net (code "78") (name "Net-(U$3-VC)") (class "Default")
      (node (ref "C2") (pin "1") (pinfunction "1_1") (pintype "passive"))
      (node (ref "R3") (pin "1") (pinfunction "1_1") (pintype "passive"))
      (node (ref "U$3") (pin "4") (pinfunction "VC_4") (pintype "bidirectional"))
    )
    (net (code "79") (name "Net-(U$3-VDD)") (class "Default")
      (node (ref "C1") (pin "1") (pinfunction "1_1") (pintype "passive"))
      (node (ref "R2") (pin "1") (pinfunction "1_1") (pintype "passive"))
      (node (ref "U$3") (pin "5") (pinfunction "VDD_5") (pintype "bidirectional"))
    )
    (net (code "80") (name "Net-(U$4-OUT)") (class "Default")
      (node (ref "U$4") (pin "6") (pinfunction "OUT_6") (pintype "bidirectional"))
      (node (ref "U$6") (pin "1") (pinfunction "G_1") (pintype "bidirectional"))
    )
    (net (code "81") (name "Net-(U$4-VDD)") (class "Default")
      (node (ref "C3") (pin "1") (pinfunction "1_1") (pintype "passive"))
      (node (ref "R6") (pin "1") (pinfunction "1_1") (pintype "passive"))
      (node (ref "U$4") (pin "2") (pinfunction "VDD_2") (pintype "bidirectional"))
    )
    (net (code "82") (name "Net-(U$4-VSS)") (class "Default")
      (node (ref "AB1") (pin "7") (pinfunction "7_7") (pintype "passive"))
      (node (ref "C3") (pin "2") (pinfunction "2_2") (pintype "passive"))
      (node (ref "R3") (pin "2") (pinfunction "2_2") (pintype "passive"))
      (node (ref "R5") (pin "2") (pinfunction "2_2") (pintype "passive"))
      (node (ref "R7") (pin "2") (pinfunction "2_2") (pintype "passive"))
      (node (ref "U$4") (pin "3") (pinfunction "VSS_3") (pintype "bidirectional"))
      (node (ref "U$6") (pin "2") (pinfunction "S_2") (pintype "bidirectional"))
    )
    (net (code "83") (name "Net-(U$5-OUT)") (class "Default")
      (node (ref "U$5") (pin "6") (pinfunction "OUT_6") (pintype "bidirectional"))
      (node (ref "U$7") (pin "1") (pinfunction "G_1") (pintype "bidirectional"))
    )
    (net (code "84") (name "Net-(U$5-VDD)") (class "Default")
      (node (ref "C4") (pin "1") (pinfunction "1_1") (pintype "passive"))
      (node (ref "R7") (pin "1") (pinfunction "1_1") (pintype "passive"))
      (node (ref "U$5") (pin "2") (pinfunction "VDD_2") (pintype "bidirectional"))
    )
    (net (code "85") (name "Net-(U$6-D)") (class "Default")
      (node (ref "R4") (pin "1") (pinfunction "1_1") (pintype "passive"))
      (node (ref "U$6") (pin "3") (pinfunction "D_3") (pintype "bidirectional"))
    )
    (net (code "86") (name "Net-(U$7-D)") (class "Default")
      (node (ref "R5") (pin "1") (pinfunction "1_1") (pintype "passive"))
      (node (ref "U$7") (pin "3") (pinfunction "D_3") (pintype "bidirectional"))
    )
    (net (code "87") (name "Net-(U$8-S2)") (class "Default")
      (node (ref "R41") (pin "2") (pinfunction "2_2") (pintype "passive"))
      (node (ref "R48") (pin "1") (pinfunction "1_1") (pintype "passive"))
      (node (ref "U$8") (pin "67") (pinfunction "S2_67") (pintype "bidirectional"))
    )
    (net (code "88") (name "Net-(U$9-G1)") (class "Default")
      (node (ref "R90") (pin "2") (pinfunction "2_2") (pintype "passive"))
      (node (ref "U$9") (pin "4") (pinfunction "G1_4") (pintype "bidirectional"))
    )
    (net (code "89") (name "Net-(U$9-G2)") (class "Default")
      (node (ref "R91") (pin "2") (pinfunction "2_2") (pintype "passive"))
      (node (ref "U$9") (pin "5") (pinfunction "G2_5") (pintype "bidirectional"))
    )
    (net (code "90") (name "Net-(U$10-CS)") (class "Default")
      (node (ref "R9") (pin "1") (pinfunction "1_1") (pintype "passive"))
      (node (ref "U$10") (pin "3") (pinfunction "CS_3") (pintype "bidirectional"))
    )
    (net (code "91") (name "Net-(U$10-VC)") (class "Default")
      (node (ref "C6") (pin "1") (pinfunction "1_1") (pintype "passive"))
      (node (ref "R11") (pin "1") (pinfunction "1_1") (pintype "passive"))
      (node (ref "U$10") (pin "4") (pinfunction "VC_4") (pintype "bidirectional"))
    )
    (net (code "92") (name "Net-(U$10-VDD)") (class "Default")
      (node (ref "C5") (pin "1") (pinfunction "1_1") (pintype "passive"))
      (node (ref "R10") (pin "1") (pinfunction "1_1") (pintype "passive"))
      (node (ref "U$10") (pin "5") (pinfunction "VDD_5") (pintype "bidirectional"))
    )
    (net (code "93") (name "Net-(U$11-OUT)") (class "Default")
      (node (ref "U$11") (pin "6") (pinfunction "OUT_6") (pintype "bidirectional"))
      (node (ref "U$13") (pin "1") (pinfunction "G_1") (pintype "bidirectional"))
    )
    (net (code "94") (name "Net-(U$11-VDD)") (class "Default")
      (node (ref "C7") (pin "1") (pinfunction "1_1") (pintype "passive"))
      (node (ref "R14") (pin "1") (pinfunction "1_1") (pintype "passive"))
      (node (ref "U$11") (pin "2") (pinfunction "VDD_2") (pintype "bidirectional"))
    )
    (net (code "95") (name "Net-(U$11-VSS)") (class "Default")
      (node (ref "AB2") (pin "7") (pinfunction "7_7") (pintype "passive"))
      (node (ref "C7") (pin "2") (pinfunction "2_2") (pintype "passive"))
      (node (ref "R11") (pin "2") (pinfunction "2_2") (pintype "passive"))
      (node (ref "R13") (pin "2") (pinfunction "2_2") (pintype "passive"))
      (node (ref "R15") (pin "2") (pinfunction "2_2") (pintype "passive"))
      (node (ref "U$11") (pin "3") (pinfunction "VSS_3") (pintype "bidirectional"))
      (node (ref "U$13") (pin "2") (pinfunction "S_2") (pintype "bidirectional"))
    )
    (net (code "96") (name "Net-(U$12-OUT)") (class "Default")
      (node (ref "U$12") (pin "6") (pinfunction "OUT_6") (pintype "bidirectional"))
      (node (ref "U$14") (pin "1") (pinfunction "G_1") (pintype "bidirectional"))
    )
    (net (code "97") (name "Net-(U$12-VDD)") (class "Default")
      (node (ref "C8") (pin "1") (pinfunction "1_1") (pintype "passive"))
      (node (ref "R15") (pin "1") (pinfunction "1_1") (pintype "passive"))
      (node (ref "U$12") (pin "2") (pinfunction "VDD_2") (pintype "bidirectional"))
    )
    (net (code "98") (name "Net-(U$13-D)") (class "Default")
      (node (ref "R12") (pin "1") (pinfunction "1_1") (pintype "passive"))
      (node (ref "U$13") (pin "3") (pinfunction "D_3") (pintype "bidirectional"))
    )
    (net (code "99") (name "Net-(U$14-D)") (class "Default")
      (node (ref "R13") (pin "1") (pinfunction "1_1") (pintype "passive"))
      (node (ref "U$14") (pin "3") (pinfunction "D_3") (pintype "bidirectional"))
    )
    (net (code "100") (name "Net-(U$15-S1)") (class "Default")
      (node (ref "U$15") (pin "23") (pinfunction "S1_23") (pintype "bidirectional"))
      (node (ref "U$22") (pin "67") (pinfunction "S2_67") (pintype "bidirectional"))
    )
    (net (code "101") (name "Net-(U$15-S2)") (class "Default")
      (node (ref "R33") (pin "2") (pinfunction "2_2") (pintype "passive"))
      (node (ref "R40") (pin "1") (pinfunction "1_1") (pintype "passive"))
      (node (ref "U$15") (pin "67") (pinfunction "S2_67") (pintype "bidirectional"))
    )
    (net (code "102") (name "Net-(U$16-BST1)") (class "Default")
      (node (ref "C13") (pin "2") (pinfunction "2_2") (pintype "passive"))
      (node (ref "U$16") (pin "26") (pinfunction "BST1_26") (pintype "bidirectional"))
    )
    (net (code "103") (name "Net-(U$16-BST2)") (class "Default")
      (node (ref "C14") (pin "2") (pinfunction "2_2") (pintype "passive"))
      (node (ref "U$16") (pin "3") (pinfunction "BST2_3") (pintype "bidirectional"))
    )
    (net (code "104") (name "Net-(U$16-RT)") (class "Default")
      (node (ref "R28") (pin "2") (pinfunction "2_2") (pintype "passive"))
      (node (ref "U$16") (pin "17") (pinfunction "RT_17") (pintype "bidirectional"))
    )
    (net (code "105") (name "Net-(U$16-VC)") (class "Default")
      (node (ref "R29") (pin "1") (pinfunction "1_1") (pintype "passive"))
      (node (ref "U$16") (pin "13") (pinfunction "VC_13") (pintype "bidirectional"))
    )
    (net (code "106") (name "Net-(U$17-CS)") (class "Default")
      (node (ref "R17") (pin "1") (pinfunction "1_1") (pintype "passive"))
      (node (ref "U$17") (pin "3") (pinfunction "CS_3") (pintype "bidirectional"))
    )
    (net (code "107") (name "Net-(U$17-VC)") (class "Default")
      (node (ref "C10") (pin "1") (pinfunction "1_1") (pintype "passive"))
      (node (ref "R19") (pin "1") (pinfunction "1_1") (pintype "passive"))
      (node (ref "U$17") (pin "4") (pinfunction "VC_4") (pintype "bidirectional"))
    )
    (net (code "108") (name "Net-(U$17-VDD)") (class "Default")
      (node (ref "C9") (pin "1") (pinfunction "1_1") (pintype "passive"))
      (node (ref "R18") (pin "1") (pinfunction "1_1") (pintype "passive"))
      (node (ref "U$17") (pin "5") (pinfunction "VDD_5") (pintype "bidirectional"))
    )
    (net (code "109") (name "Net-(U$18-OUT)") (class "Default")
      (node (ref "U$18") (pin "6") (pinfunction "OUT_6") (pintype "bidirectional"))
      (node (ref "U$20") (pin "1") (pinfunction "G_1") (pintype "bidirectional"))
    )
    (net (code "110") (name "Net-(U$18-VDD)") (class "Default")
      (node (ref "C11") (pin "1") (pinfunction "1_1") (pintype "passive"))
      (node (ref "R22") (pin "1") (pinfunction "1_1") (pintype "passive"))
      (node (ref "U$18") (pin "2") (pinfunction "VDD_2") (pintype "bidirectional"))
    )
    (net (code "111") (name "Net-(U$18-VSS)") (class "Default")
      (node (ref "AB3") (pin "7") (pinfunction "7_7") (pintype "passive"))
      (node (ref "C11") (pin "2") (pinfunction "2_2") (pintype "passive"))
      (node (ref "R19") (pin "2") (pinfunction "2_2") (pintype "passive"))
      (node (ref "R21") (pin "2") (pinfunction "2_2") (pintype "passive"))
      (node (ref "R23") (pin "2") (pinfunction "2_2") (pintype "passive"))
      (node (ref "U$18") (pin "3") (pinfunction "VSS_3") (pintype "bidirectional"))
      (node (ref "U$20") (pin "2") (pinfunction "S_2") (pintype "bidirectional"))
    )
    (net (code "112") (name "Net-(U$19-OUT)") (class "Default")
      (node (ref "U$19") (pin "6") (pinfunction "OUT_6") (pintype "bidirectional"))
      (node (ref "U$21") (pin "1") (pinfunction "G_1") (pintype "bidirectional"))
    )
    (net (code "113") (name "Net-(U$19-VDD)") (class "Default")
      (node (ref "C12") (pin "1") (pinfunction "1_1") (pintype "passive"))
      (node (ref "R23") (pin "1") (pinfunction "1_1") (pintype "passive"))
      (node (ref "U$19") (pin "2") (pinfunction "VDD_2") (pintype "bidirectional"))
    )
    (net (code "114") (name "Net-(U$20-D)") (class "Default")
      (node (ref "R20") (pin "1") (pinfunction "1_1") (pintype "passive"))
      (node (ref "U$20") (pin "3") (pinfunction "D_3") (pintype "bidirectional"))
    )
    (net (code "115") (name "Net-(U$21-D)") (class "Default")
      (node (ref "R21") (pin "1") (pinfunction "1_1") (pintype "passive"))
      (node (ref "U$21") (pin "3") (pinfunction "D_3") (pintype "bidirectional"))
    )
    (net (code "116") (name "Net-(U$22-G1)") (class "Default")
      (node (ref "R88") (pin "2") (pinfunction "2_2") (pintype "passive"))
      (node (ref "U$22") (pin "4") (pinfunction "G1_4") (pintype "bidirectional"))
    )
    (net (code "117") (name "Net-(U$22-G2)") (class "Default")
      (node (ref "R89") (pin "2") (pinfunction "2_2") (pintype "passive"))
      (node (ref "U$22") (pin "5") (pinfunction "G2_5") (pintype "bidirectional"))
    )
    (net (code "118") (name "Net-(U$24-S1)") (class "Default")
      (node (ref "U$24") (pin "23") (pinfunction "S1_23") (pintype "bidirectional"))
      (node (ref "U$9") (pin "67") (pinfunction "S2_67") (pintype "bidirectional"))
    )
    (net (code "119") (name "Net-(U$24-S2)") (class "Default")
      (node (ref "R17") (pin "2") (pinfunction "2_2") (pintype "passive"))
      (node (ref "R24") (pin "1") (pinfunction "1_1") (pintype "passive"))
      (node (ref "U$24") (pin "67") (pinfunction "S2_67") (pintype "bidirectional"))
    )
    (net (code "120") (name "Net-(U$25-S1)") (class "Default")
      (node (ref "U$25") (pin "23") (pinfunction "S1_23") (pintype "bidirectional"))
      (node (ref "U$27") (pin "67") (pinfunction "S2_67") (pintype "bidirectional"))
    )
    (net (code "121") (name "Net-(U$25-S2)") (class "Default")
      (node (ref "R16") (pin "1") (pinfunction "1_1") (pintype "passive"))
      (node (ref "R9") (pin "2") (pinfunction "2_2") (pintype "passive"))
      (node (ref "U$25") (pin "67") (pinfunction "S2_67") (pintype "bidirectional"))
    )
    (net (code "122") (name "Net-(U$26-S1)") (class "Default")
      (node (ref "U$26") (pin "23") (pinfunction "S1_23") (pintype "bidirectional"))
      (node (ref "U$29") (pin "67") (pinfunction "S2_67") (pintype "bidirectional"))
    )
    (net (code "123") (name "Net-(U$26-S2)") (class "Default")
      (node (ref "R1") (pin "2") (pinfunction "2_2") (pintype "passive"))
      (node (ref "R8") (pin "1") (pinfunction "1_1") (pintype "passive"))
      (node (ref "U$26") (pin "67") (pinfunction "S2_67") (pintype "bidirectional"))
    )
    (net (code "124") (name "Net-(U$27-G1)") (class "Default")
      (node (ref "R92") (pin "2") (pinfunction "2_2") (pintype "passive"))
      (node (ref "U$27") (pin "4") (pinfunction "G1_4") (pintype "bidirectional"))
    )
    (net (code "125") (name "Net-(U$27-G2)") (class "Default")
      (node (ref "R93") (pin "2") (pinfunction "2_2") (pintype "passive"))
      (node (ref "U$27") (pin "5") (pinfunction "G2_5") (pintype "bidirectional"))
    )
    (net (code "126") (name "Net-(U$28-G1)") (class "Default")
      (node (ref "R96") (pin "2") (pinfunction "2_2") (pintype "passive"))
      (node (ref "U$28") (pin "4") (pinfunction "G1_4") (pintype "bidirectional"))
    )
    (net (code "127") (name "Net-(U$28-G2)") (class "Default")
      (node (ref "R97") (pin "2") (pinfunction "2_2") (pintype "passive"))
      (node (ref "U$28") (pin "5") (pinfunction "G2_5") (pintype "bidirectional"))
    )
    (net (code "128") (name "Net-(U$28-S2)") (class "Default")
      (node (ref "U$28") (pin "67") (pinfunction "S2_67") (pintype "bidirectional"))
      (node (ref "U$8") (pin "23") (pinfunction "S1_23") (pintype "bidirectional"))
    )
    (net (code "129") (name "Net-(U$29-G1)") (class "Default")
      (node (ref "R94") (pin "2") (pinfunction "2_2") (pintype "passive"))
      (node (ref "U$29") (pin "4") (pinfunction "G1_4") (pintype "bidirectional"))
    )
    (net (code "130") (name "Net-(U$29-G2)") (class "Default")
      (node (ref "R95") (pin "2") (pinfunction "2_2") (pintype "passive"))
      (node (ref "U$29") (pin "5") (pinfunction "G2_5") (pintype "bidirectional"))
    )
    (net (code "131") (name "Net-(U$30-G1)") (class "Default")
      (node (ref "R98") (pin "2") (pinfunction "2_2") (pintype "passive"))
      (node (ref "U$30") (pin "4") (pinfunction "G1_4") (pintype "bidirectional"))
    )
    (net (code "132") (name "Net-(U$30-G2)") (class "Default")
      (node (ref "R99") (pin "2") (pinfunction "2_2") (pintype "passive"))
      (node (ref "U$30") (pin "5") (pinfunction "G2_5") (pintype "bidirectional"))
    )
    (net (code "133") (name "Net-(U$31-CS)") (class "Default")
      (node (ref "R33") (pin "1") (pinfunction "1_1") (pintype "passive"))
      (node (ref "U$31") (pin "3") (pinfunction "CS_3") (pintype "bidirectional"))
    )
    (net (code "134") (name "Net-(U$31-VC)") (class "Default")
      (node (ref "C18") (pin "1") (pinfunction "1_1") (pintype "passive"))
      (node (ref "R35") (pin "1") (pinfunction "1_1") (pintype "passive"))
      (node (ref "U$31") (pin "4") (pinfunction "VC_4") (pintype "bidirectional"))
    )
    (net (code "135") (name "Net-(U$31-VDD)") (class "Default")
      (node (ref "C17") (pin "1") (pinfunction "1_1") (pintype "passive"))
      (node (ref "R34") (pin "1") (pinfunction "1_1") (pintype "passive"))
      (node (ref "U$31") (pin "5") (pinfunction "VDD_5") (pintype "bidirectional"))
    )
    (net (code "136") (name "Net-(U$32-OUT)") (class "Default")
      (node (ref "U$32") (pin "6") (pinfunction "OUT_6") (pintype "bidirectional"))
      (node (ref "U$34") (pin "1") (pinfunction "G_1") (pintype "bidirectional"))
    )
    (net (code "137") (name "Net-(U$32-VDD)") (class "Default")
      (node (ref "C19") (pin "1") (pinfunction "1_1") (pintype "passive"))
      (node (ref "R38") (pin "1") (pinfunction "1_1") (pintype "passive"))
      (node (ref "U$32") (pin "2") (pinfunction "VDD_2") (pintype "bidirectional"))
    )
    (net (code "138") (name "Net-(U$32-VSS)") (class "Default")
      (node (ref "AB3") (pin "2") (pinfunction "2_2") (pintype "passive"))
      (node (ref "C19") (pin "2") (pinfunction "2_2") (pintype "passive"))
      (node (ref "R35") (pin "2") (pinfunction "2_2") (pintype "passive"))
      (node (ref "R37") (pin "2") (pinfunction "2_2") (pintype "passive"))
      (node (ref "R39") (pin "2") (pinfunction "2_2") (pintype "passive"))
      (node (ref "U$32") (pin "3") (pinfunction "VSS_3") (pintype "bidirectional"))
      (node (ref "U$34") (pin "2") (pinfunction "S_2") (pintype "bidirectional"))
    )
    (net (code "139") (name "Net-(U$33-OUT)") (class "Default")
      (node (ref "U$33") (pin "6") (pinfunction "OUT_6") (pintype "bidirectional"))
      (node (ref "U$35") (pin "1") (pinfunction "G_1") (pintype "bidirectional"))
    )
    (net (code "140") (name "Net-(U$33-VDD)") (class "Default")
      (node (ref "C20") (pin "1") (pinfunction "1_1") (pintype "passive"))
      (node (ref "R39") (pin "1") (pinfunction "1_1") (pintype "passive"))
      (node (ref "U$33") (pin "2") (pinfunction "VDD_2") (pintype "bidirectional"))
    )
    (net (code "141") (name "Net-(U$34-D)") (class "Default")
      (node (ref "R36") (pin "1") (pinfunction "1_1") (pintype "passive"))
      (node (ref "U$34") (pin "3") (pinfunction "D_3") (pintype "bidirectional"))
    )
    (net (code "142") (name "Net-(U$35-D)") (class "Default")
      (node (ref "R37") (pin "1") (pinfunction "1_1") (pintype "passive"))
      (node (ref "U$35") (pin "3") (pinfunction "D_3") (pintype "bidirectional"))
    )
    (net (code "143") (name "Net-(U$38-CS)") (class "Default")
      (node (ref "R41") (pin "1") (pinfunction "1_1") (pintype "passive"))
      (node (ref "U$38") (pin "3") (pinfunction "CS_3") (pintype "bidirectional"))
    )
    (net (code "144") (name "Net-(U$38-VC)") (class "Default")
      (node (ref "C22") (pin "1") (pinfunction "1_1") (pintype "passive"))
      (node (ref "R43") (pin "1") (pinfunction "1_1") (pintype "passive"))
      (node (ref "U$38") (pin "4") (pinfunction "VC_4") (pintype "bidirectional"))
    )
    (net (code "145") (name "Net-(U$38-VDD)") (class "Default")
      (node (ref "C21") (pin "1") (pinfunction "1_1") (pintype "passive"))
      (node (ref "R42") (pin "1") (pinfunction "1_1") (pintype "passive"))
      (node (ref "U$38") (pin "5") (pinfunction "VDD_5") (pintype "bidirectional"))
    )
    (net (code "146") (name "Net-(U$39-OUT)") (class "Default")
      (node (ref "U$39") (pin "6") (pinfunction "OUT_6") (pintype "bidirectional"))
      (node (ref "U$41") (pin "1") (pinfunction "G_1") (pintype "bidirectional"))
    )
    (net (code "147") (name "Net-(U$39-VDD)") (class "Default")
      (node (ref "C23") (pin "1") (pinfunction "1_1") (pintype "passive"))
      (node (ref "R46") (pin "1") (pinfunction "1_1") (pintype "passive"))
      (node (ref "U$39") (pin "2") (pinfunction "VDD_2") (pintype "bidirectional"))
    )
    (net (code "148") (name "Net-(U$39-VSS)") (class "Default")
      (node (ref "AB2") (pin "2") (pinfunction "2_2") (pintype "passive"))
      (node (ref "C23") (pin "2") (pinfunction "2_2") (pintype "passive"))
      (node (ref "R43") (pin "2") (pinfunction "2_2") (pintype "passive"))
      (node (ref "R45") (pin "2") (pinfunction "2_2") (pintype "passive"))
      (node (ref "R47") (pin "2") (pinfunction "2_2") (pintype "passive"))
      (node (ref "U$39") (pin "3") (pinfunction "VSS_3") (pintype "bidirectional"))
      (node (ref "U$41") (pin "2") (pinfunction "S_2") (pintype "bidirectional"))
    )
    (net (code "149") (name "Net-(U$40-OUT)") (class "Default")
      (node (ref "U$40") (pin "6") (pinfunction "OUT_6") (pintype "bidirectional"))
      (node (ref "U$42") (pin "1") (pinfunction "G_1") (pintype "bidirectional"))
    )
    (net (code "150") (name "Net-(U$40-VDD)") (class "Default")
      (node (ref "C24") (pin "1") (pinfunction "1_1") (pintype "passive"))
      (node (ref "R47") (pin "1") (pinfunction "1_1") (pintype "passive"))
      (node (ref "U$40") (pin "2") (pinfunction "VDD_2") (pintype "bidirectional"))
    )
    (net (code "151") (name "Net-(U$41-D)") (class "Default")
      (node (ref "R44") (pin "1") (pinfunction "1_1") (pintype "passive"))
      (node (ref "U$41") (pin "3") (pinfunction "D_3") (pintype "bidirectional"))
    )
    (net (code "152") (name "Net-(U$42-D)") (class "Default")
      (node (ref "R45") (pin "1") (pinfunction "1_1") (pintype "passive"))
      (node (ref "U$42") (pin "3") (pinfunction "D_3") (pintype "bidirectional"))
    )
    (net (code "153") (name "Net-(U$45-CS)") (class "Default")
      (node (ref "R49") (pin "1") (pinfunction "1_1") (pintype "passive"))
      (node (ref "U$45") (pin "3") (pinfunction "CS_3") (pintype "bidirectional"))
    )
    (net (code "154") (name "Net-(U$45-VC)") (class "Default")
      (node (ref "C26") (pin "1") (pinfunction "1_1") (pintype "passive"))
      (node (ref "R51") (pin "1") (pinfunction "1_1") (pintype "passive"))
      (node (ref "U$45") (pin "4") (pinfunction "VC_4") (pintype "bidirectional"))
    )
    (net (code "155") (name "Net-(U$45-VDD)") (class "Default")
      (node (ref "C25") (pin "1") (pinfunction "1_1") (pintype "passive"))
      (node (ref "R50") (pin "1") (pinfunction "1_1") (pintype "passive"))
      (node (ref "U$45") (pin "5") (pinfunction "VDD_5") (pintype "bidirectional"))
    )
    (net (code "156") (name "Net-(U$46-OUT)") (class "Default")
      (node (ref "U$46") (pin "6") (pinfunction "OUT_6") (pintype "bidirectional"))
      (node (ref "U$48") (pin "1") (pinfunction "G_1") (pintype "bidirectional"))
    )
    (net (code "157") (name "Net-(U$46-VDD)") (class "Default")
      (node (ref "C27") (pin "1") (pinfunction "1_1") (pintype "passive"))
      (node (ref "R54") (pin "1") (pinfunction "1_1") (pintype "passive"))
      (node (ref "U$46") (pin "2") (pinfunction "VDD_2") (pintype "bidirectional"))
    )
    (net (code "158") (name "Net-(U$46-VSS)") (class "Default")
      (node (ref "AB1") (pin "2") (pinfunction "2_2") (pintype "passive"))
      (node (ref "C27") (pin "2") (pinfunction "2_2") (pintype "passive"))
      (node (ref "R51") (pin "2") (pinfunction "2_2") (pintype "passive"))
      (node (ref "R53") (pin "2") (pinfunction "2_2") (pintype "passive"))
      (node (ref "R55") (pin "2") (pinfunction "2_2") (pintype "passive"))
      (node (ref "U$46") (pin "3") (pinfunction "VSS_3") (pintype "bidirectional"))
      (node (ref "U$48") (pin "2") (pinfunction "S_2") (pintype "bidirectional"))
    )
    (net (code "159") (name "Net-(U$47-OUT)") (class "Default")
      (node (ref "U$47") (pin "6") (pinfunction "OUT_6") (pintype "bidirectional"))
      (node (ref "U$49") (pin "1") (pinfunction "G_1") (pintype "bidirectional"))
    )
    (net (code "160") (name "Net-(U$47-VDD)") (class "Default")
      (node (ref "C28") (pin "1") (pinfunction "1_1") (pintype "passive"))
      (node (ref "R55") (pin "1") (pinfunction "1_1") (pintype "passive"))
      (node (ref "U$47") (pin "2") (pinfunction "VDD_2") (pintype "bidirectional"))
    )
    (net (code "161") (name "Net-(U$48-D)") (class "Default")
      (node (ref "R52") (pin "1") (pinfunction "1_1") (pintype "passive"))
      (node (ref "U$48") (pin "3") (pinfunction "D_3") (pintype "bidirectional"))
    )
    (net (code "162") (name "Net-(U$49-D)") (class "Default")
      (node (ref "R53") (pin "1") (pinfunction "1_1") (pintype "passive"))
      (node (ref "U$49") (pin "3") (pinfunction "D_3") (pintype "bidirectional"))
    )
    (net (code "163") (name "Net-(U$57-IN+)") (class "Default")
      (node (ref "C41") (pin "1") (pinfunction "1_1") (pintype "passive"))
      (node (ref "R76") (pin "2") (pinfunction "2_2") (pintype "passive"))
      (node (ref "U$57") (pin "1") (pinfunction "IN+_1") (pintype "bidirectional"))
    )
    (net (code "164") (name "Net-(U$57-IN-)") (class "Default")
      (node (ref "C41") (pin "2") (pinfunction "2_2") (pintype "passive"))
      (node (ref "R77") (pin "2") (pinfunction "2_2") (pintype "passive"))
      (node (ref "U$57") (pin "2") (pinfunction "IN-_2") (pintype "bidirectional"))
    )
    (net (code "165") (name "Net-(U$59-BST1)") (class "Default")
      (node (ref "C33") (pin "2") (pinfunction "2_2") (pintype "passive"))
      (node (ref "U$59") (pin "26") (pinfunction "BST1_26") (pintype "bidirectional"))
    )
    (net (code "166") (name "Net-(U$59-BST2)") (class "Default")
      (node (ref "C34") (pin "2") (pinfunction "2_2") (pintype "passive"))
      (node (ref "U$59") (pin "3") (pinfunction "BST2_3") (pintype "bidirectional"))
    )
    (net (code "167") (name "Net-(U$59-FB)") (class "Default")
      (node (ref "R70") (pin "1") (pinfunction "1_1") (pintype "passive"))
      (node (ref "R72") (pin "1") (pinfunction "1_1") (pintype "passive"))
      (node (ref "U$59") (pin "12") (pinfunction "FB_12") (pintype "bidirectional"))
    )
    (net (code "168") (name "Net-(U$59-RT)") (class "Default")
      (node (ref "R68") (pin "2") (pinfunction "2_2") (pintype "passive"))
      (node (ref "U$59") (pin "17") (pinfunction "RT_17") (pintype "bidirectional"))
    )
    (net (code "169") (name "Net-(U$59-RUN)") (class "Default")
      (node (ref "R62") (pin "2") (pinfunction "2_2") (pintype "passive"))
      (node (ref "R87") (pin "1") (pinfunction "1_1") (pintype "passive"))
      (node (ref "U$59") (pin "18") (pinfunction "RUN_18") (pintype "bidirectional"))
    )
    (net (code "170") (name "Net-(U$59-VC)") (class "Default")
      (node (ref "R69") (pin "1") (pinfunction "1_1") (pintype "passive"))
      (node (ref "U$59") (pin "13") (pinfunction "VC_13") (pintype "bidirectional"))
    )
    (net (code "171") (name "unconnected-(IC2-PA0-WKUP-Pad10)") (class "Default")
      (node (ref "IC2") (pin "10") (pinfunction "PA0-WKUP_10") (pintype "bidirectional"))
    )
    (net (code "172") (name "unconnected-(IC2-PA8-Pad29)") (class "Default")
      (node (ref "IC2") (pin "29") (pinfunction "PA8_29") (pintype "bidirectional"))
    )
    (net (code "173") (name "unconnected-(IC2-PA11-Pad32)") (class "Default")
      (node (ref "IC2") (pin "32") (pinfunction "PA11_32") (pintype "bidirectional"))
    )
    (net (code "174") (name "unconnected-(IC2-PA12-Pad33)") (class "Default")
      (node (ref "IC2") (pin "33") (pinfunction "PA12_33") (pintype "bidirectional"))
    )
    (net (code "175") (name "unconnected-(IC2-PA15-Pad38)") (class "Default")
      (node (ref "IC2") (pin "38") (pinfunction "PA15_38") (pintype "bidirectional"))
    )
    (net (code "176") (name "unconnected-(IC2-PB3-Pad39)") (class "Default")
      (node (ref "IC2") (pin "39") (pinfunction "PB3_39") (pintype "bidirectional"))
    )
    (net (code "177") (name "unconnected-(IC2-PB4-Pad40)") (class "Default")
      (node (ref "IC2") (pin "40") (pinfunction "PB4_40") (pintype "bidirectional"))
    )
    (net (code "178") (name "unconnected-(IC2-PB12-Pad25)") (class "Default")
      (node (ref "IC2") (pin "25") (pinfunction "PB12_25") (pintype "bidirectional"))
    )
    (net (code "179") (name "unconnected-(IC2-PB13-Pad26)") (class "Default")
      (node (ref "IC2") (pin "26") (pinfunction "PB13_26") (pintype "bidirectional"))
    )
    (net (code "180") (name "unconnected-(IC2-PB14-Pad27)") (class "Default")
      (node (ref "IC2") (pin "27") (pinfunction "PB14_27") (pintype "bidirectional"))
    )
    (net (code "181") (name "unconnected-(IC2-PC13-Pad2)") (class "Default")
      (node (ref "IC2") (pin "2") (pinfunction "PC13_2") (pintype "bidirectional"))
    )
    (net (code "182") (name "unconnected-(MICRO-2-PadD-)") (class "Default")
      (node (ref "MICRO") (pin "D-") (pinfunction "2_D-") (pintype "passive"))
    )
    (net (code "183") (name "unconnected-(MICRO-3-PadD+)") (class "Default")
      (node (ref "MICRO") (pin "D+") (pinfunction "3_D+") (pintype "passive"))
    )
    (net (code "184") (name "unconnected-(MICRO-4-PadSENSE)") (class "Default")
      (node (ref "MICRO") (pin "SENSE") (pinfunction "4_SENSE") (pintype "passive"))
    )
    (net (code "185") (name "unconnected-(S1-S-Pad3)") (class "Default")
      (node (ref "S1") (pin "3") (pinfunction "S_3") (pintype "passive"))
    )
    (net (code "186") (name "unconnected-(U$2-NC-PadP$1)") (class "Default")
      (node (ref "U$2") (pin "P$1") (pinfunction "NC_P$1") (pintype "bidirectional"))
    )
    (net (code "187") (name "unconnected-(U$23-PadNC{slash}3V3)") (class "Default")
      (node (ref "U$23") (pin "NC/3V3") (pinfunction "NC/3V3_NC/3V3") (pintype "bidirectional"))
    )
    (net (code "188") (name "unconnected-(U$23-PadNC{slash}GPIO)") (class "Default")
      (node (ref "U$23") (pin "NC/GPIO") (pinfunction "NC/GPIO_NC/GPIO") (pintype "bidirectional"))
    )
    (net (code "189") (name "unconnected-(U$23-PadNC{slash}M1)") (class "Default")
      (node (ref "U$23") (pin "NC/M1") (pinfunction "NC/M1_NC/M1") (pintype "bidirectional"))
    )
  )
)
